# piksi.net
KiCad netlist of a schematic drawn in EAGLE
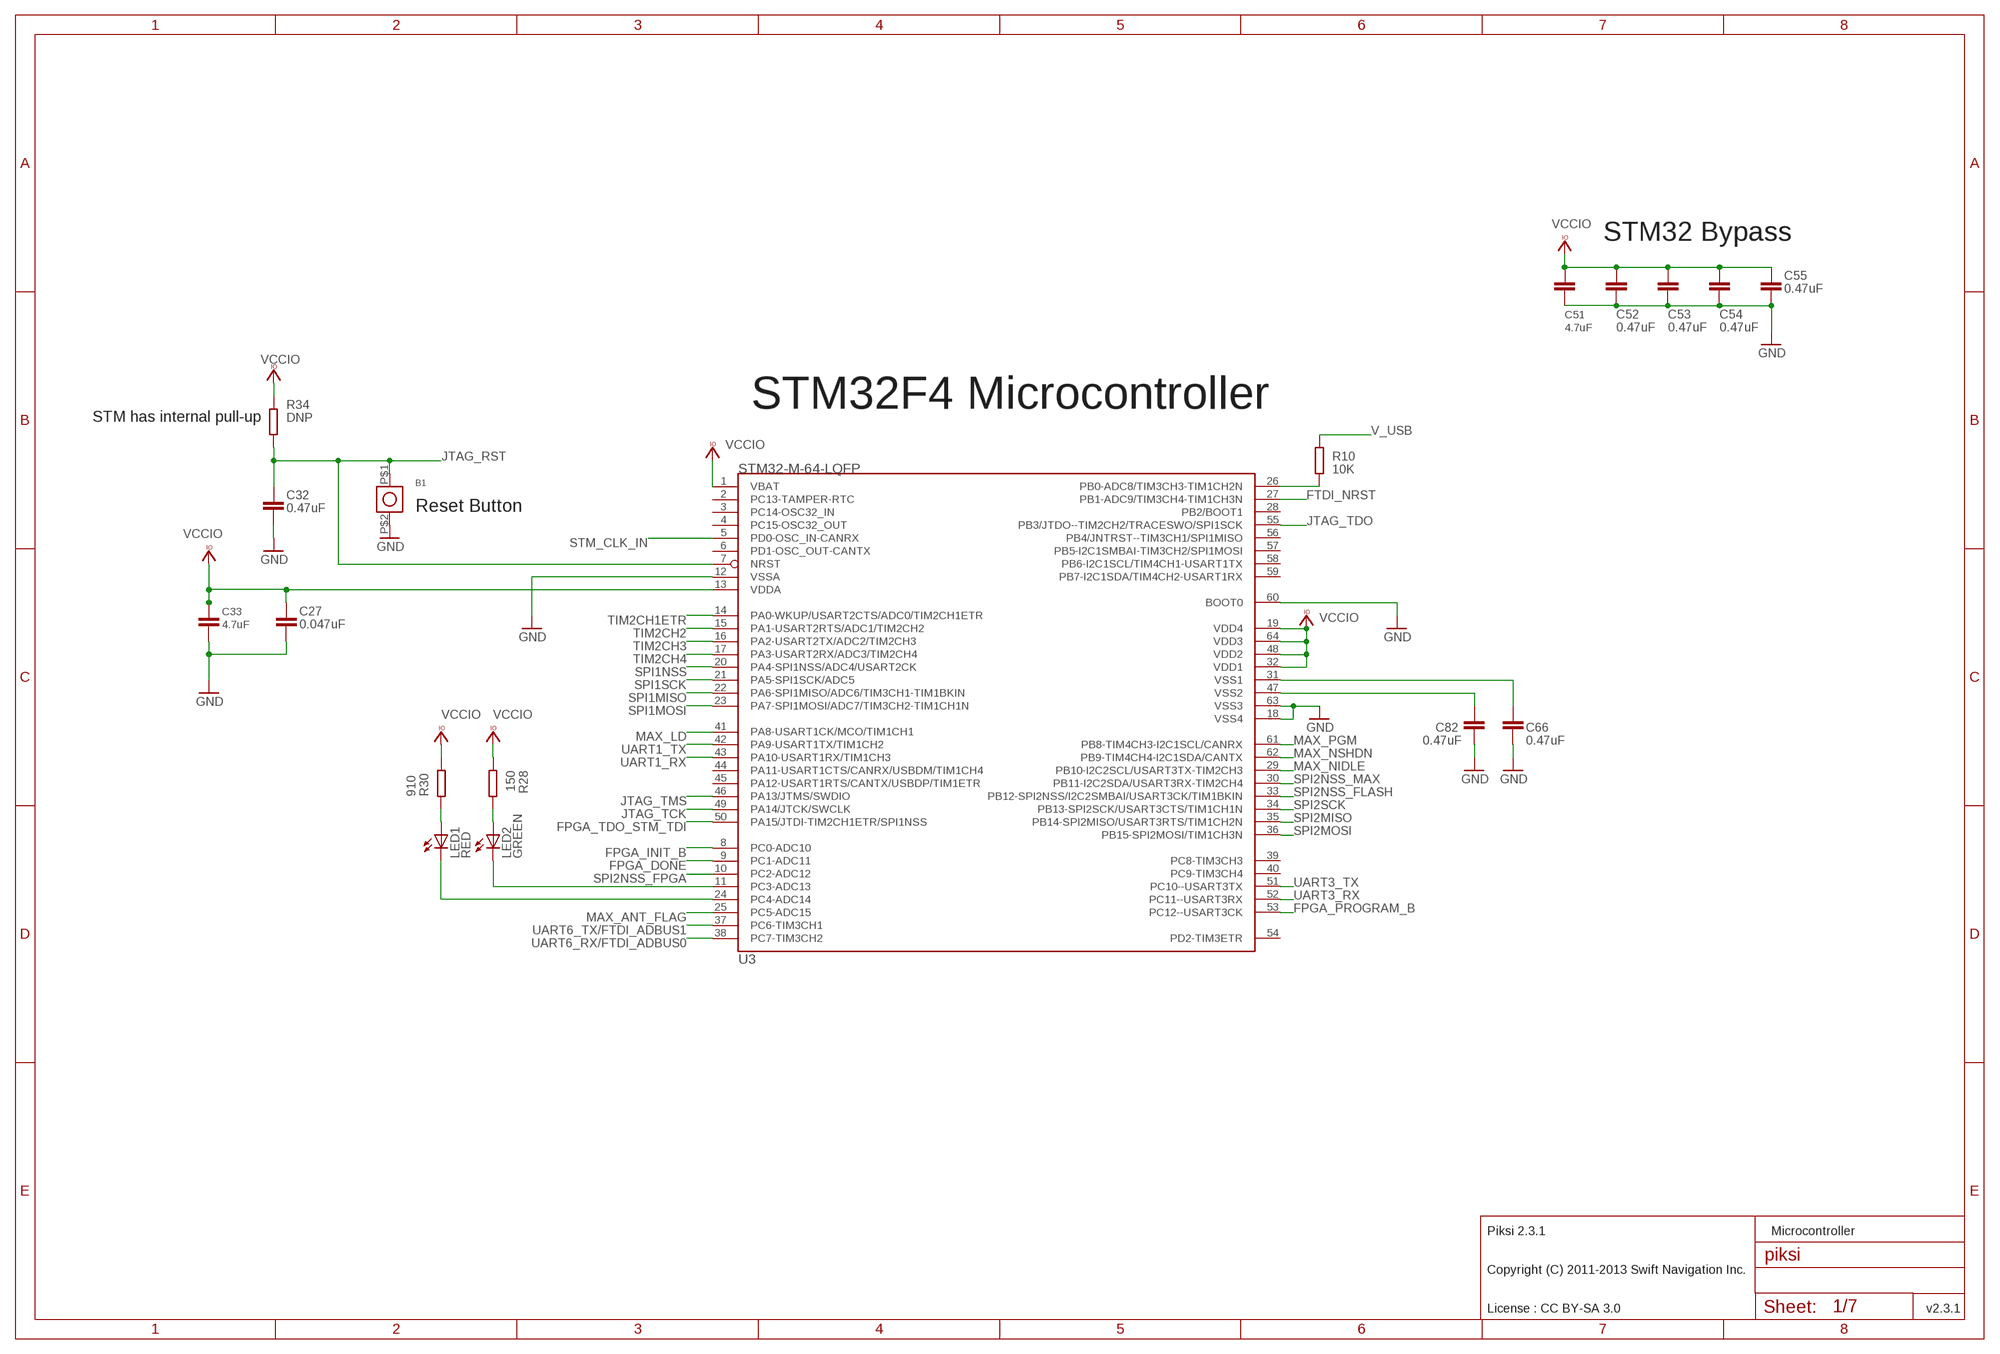
[diagram p0: schematic, sheet 1]
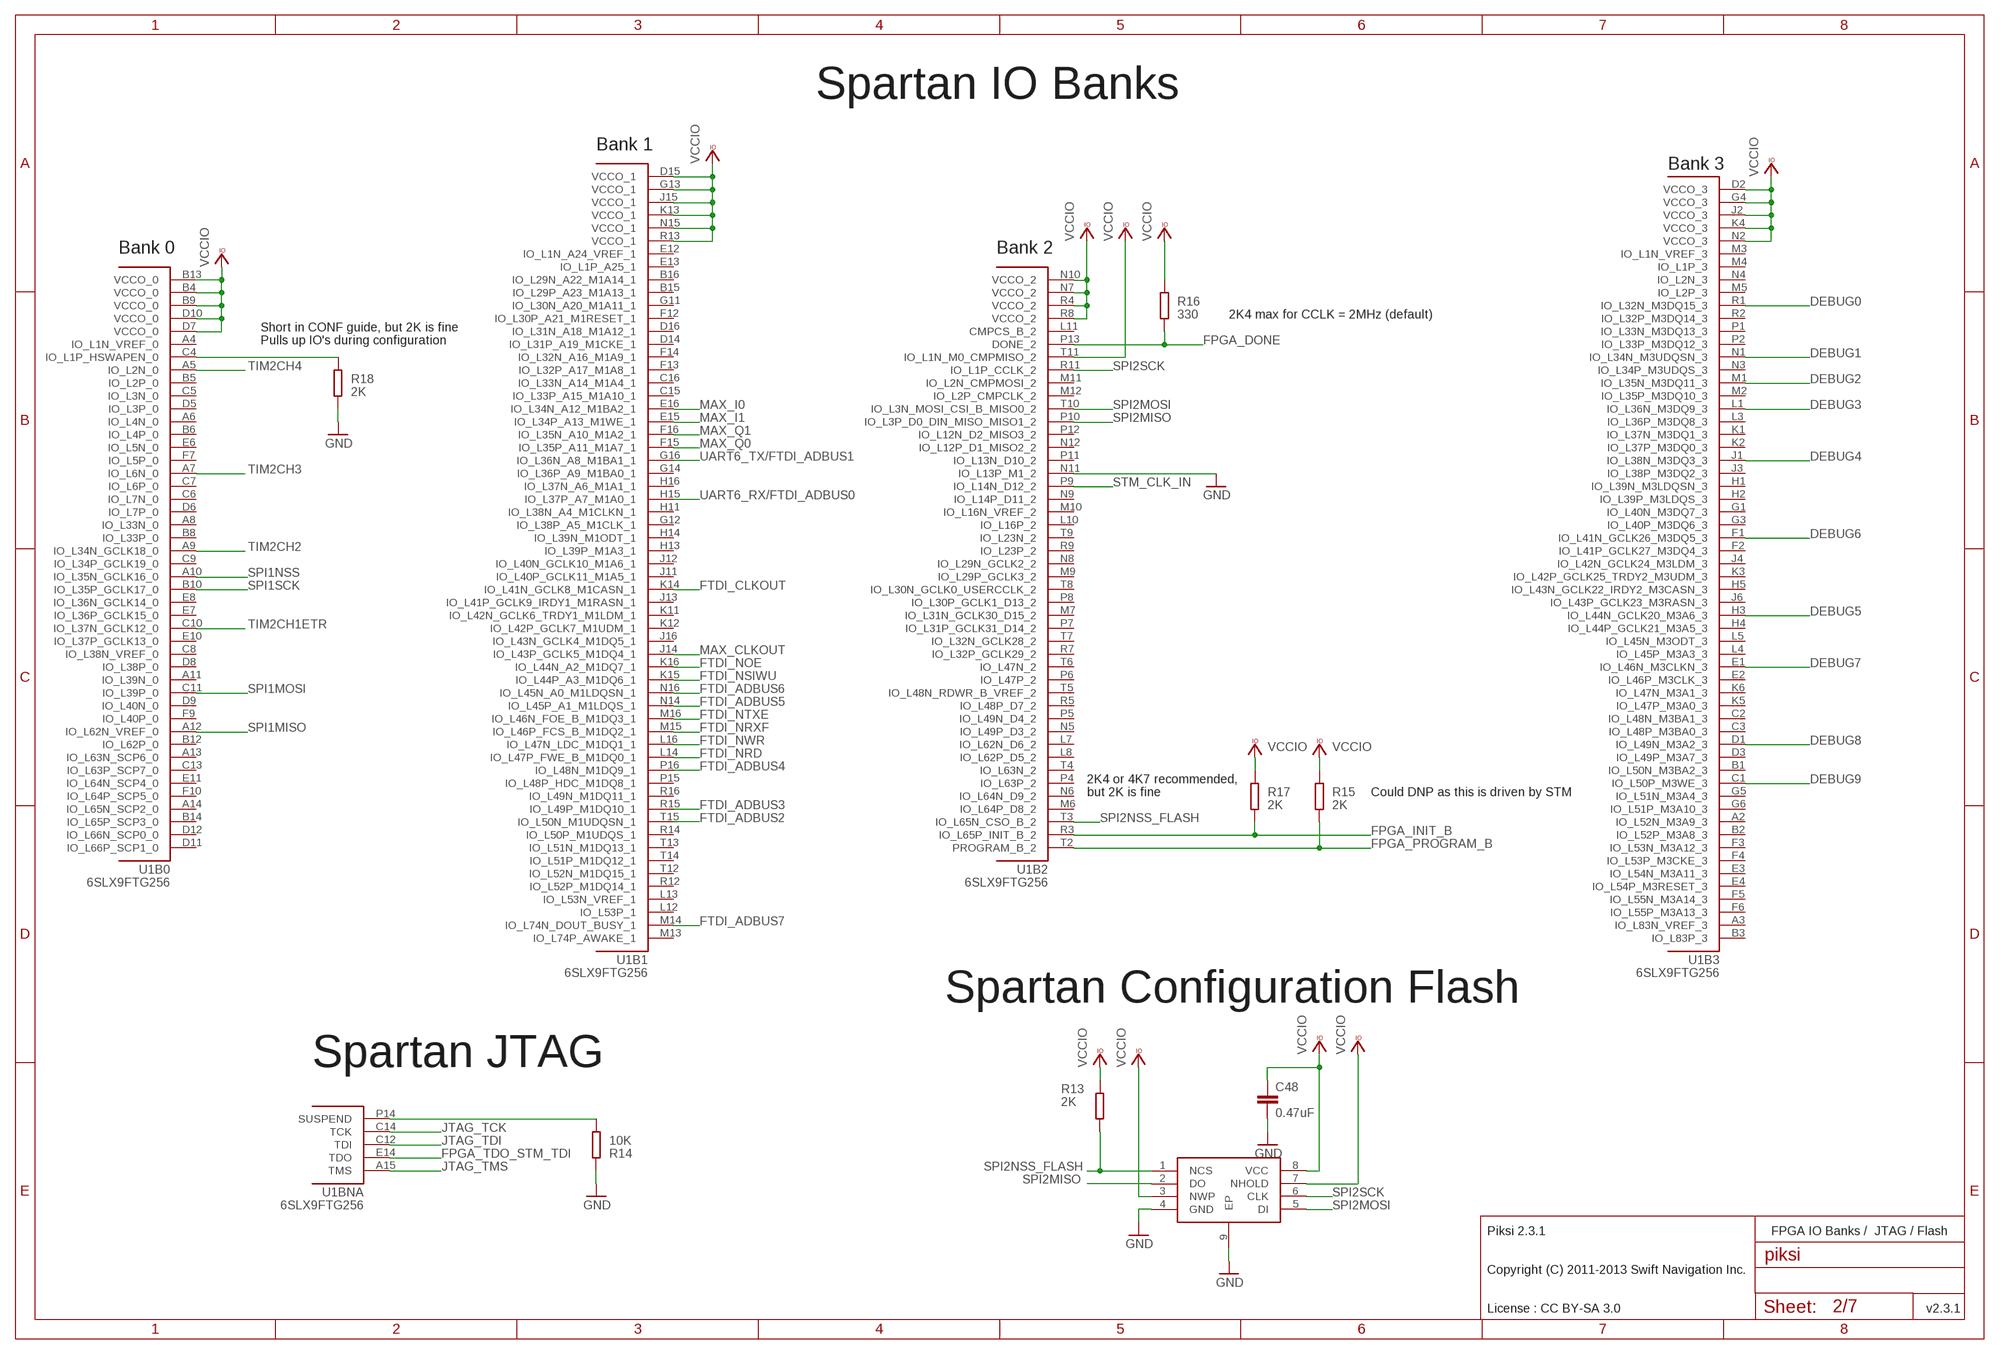
[diagram p1: schematic, sheet 2]
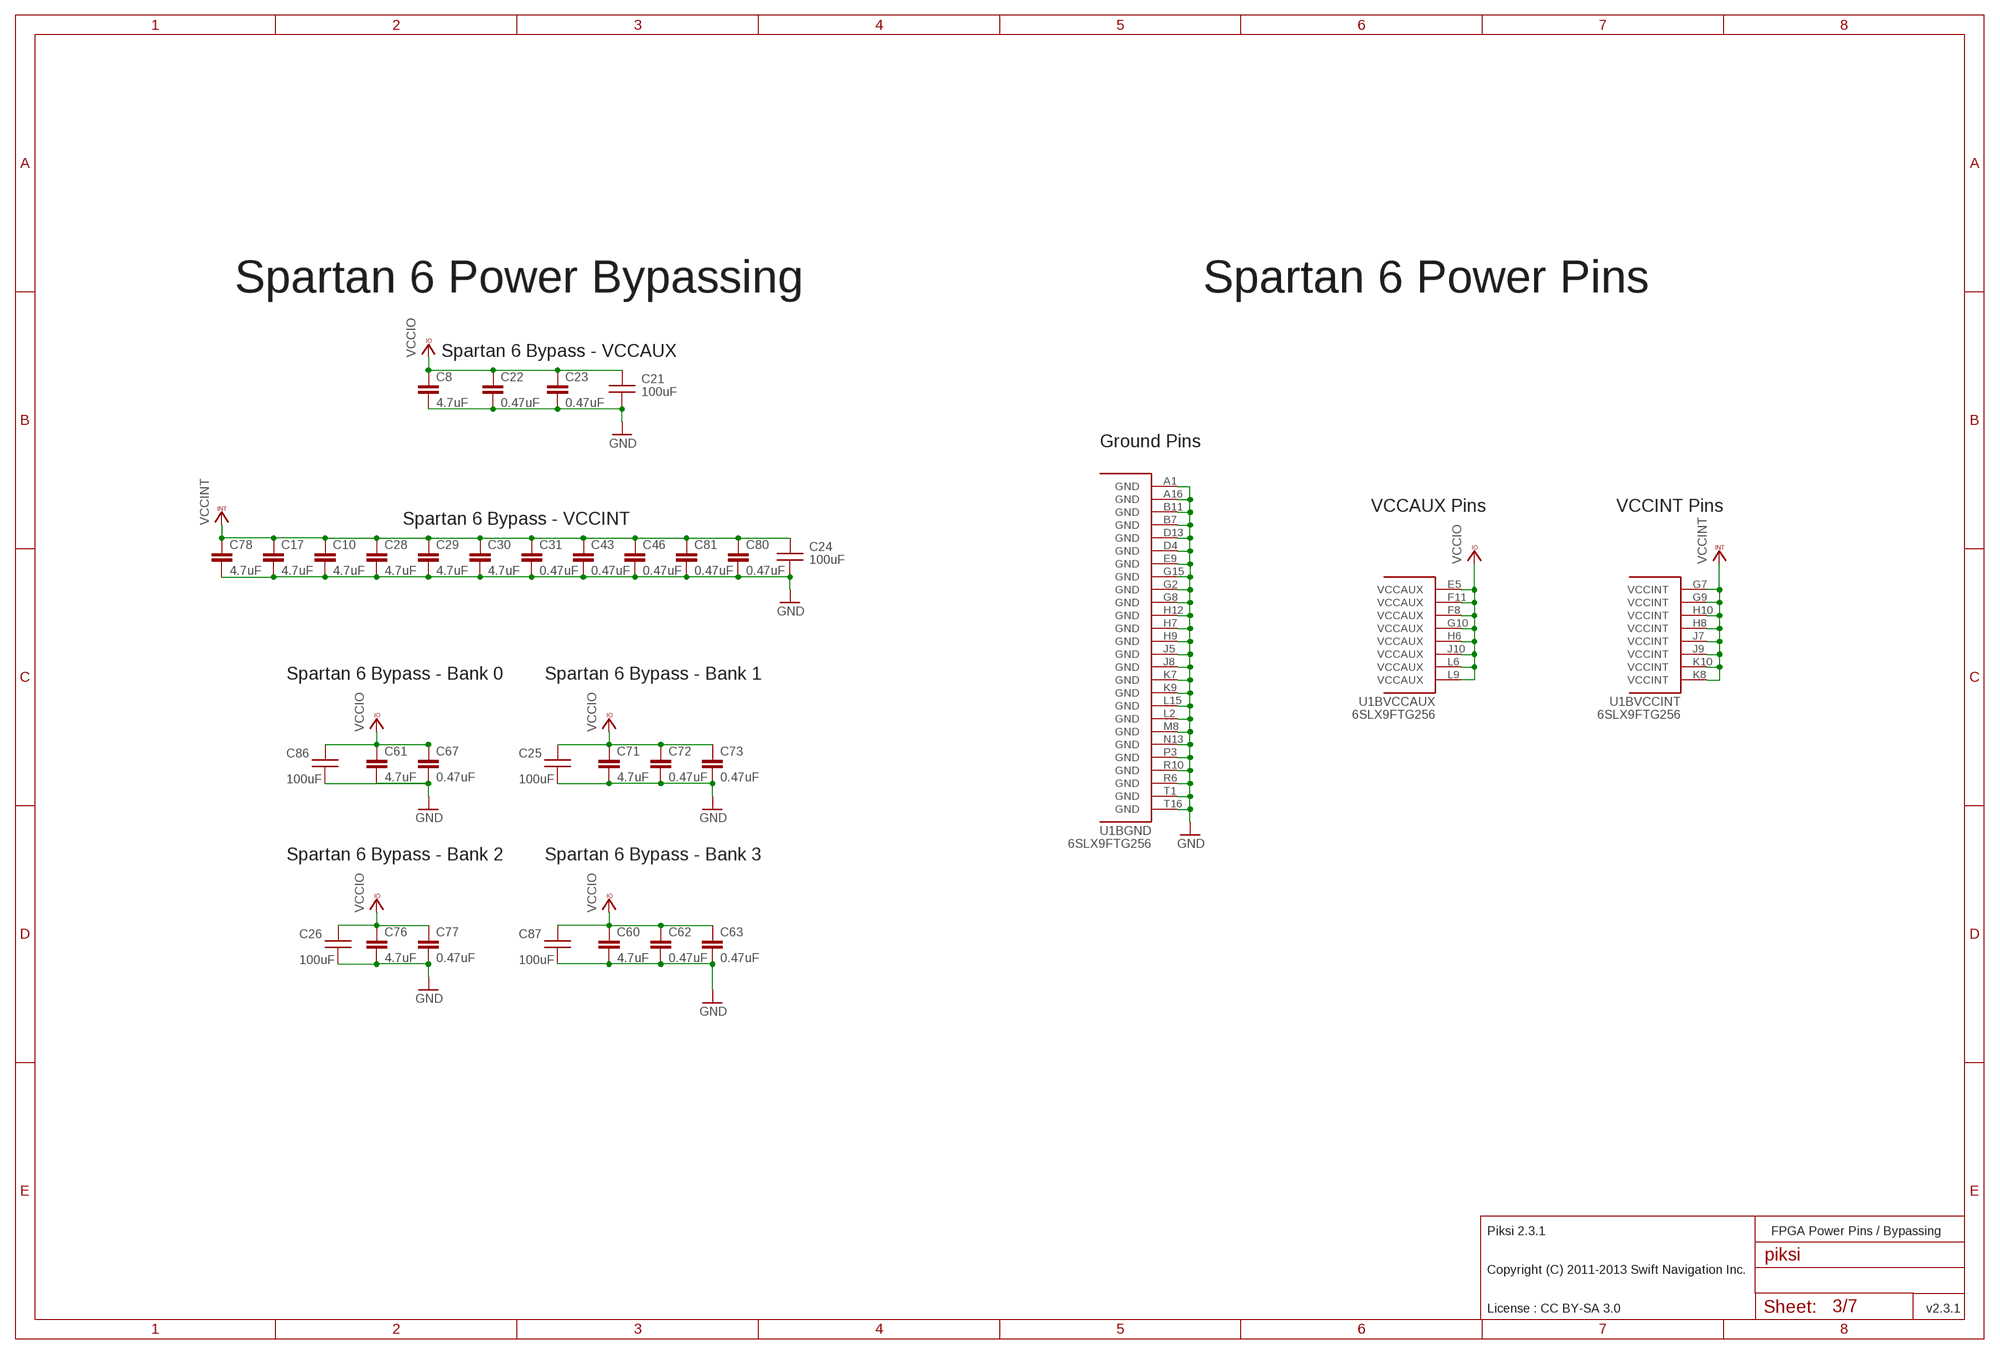
[diagram p2: schematic, sheet 3]
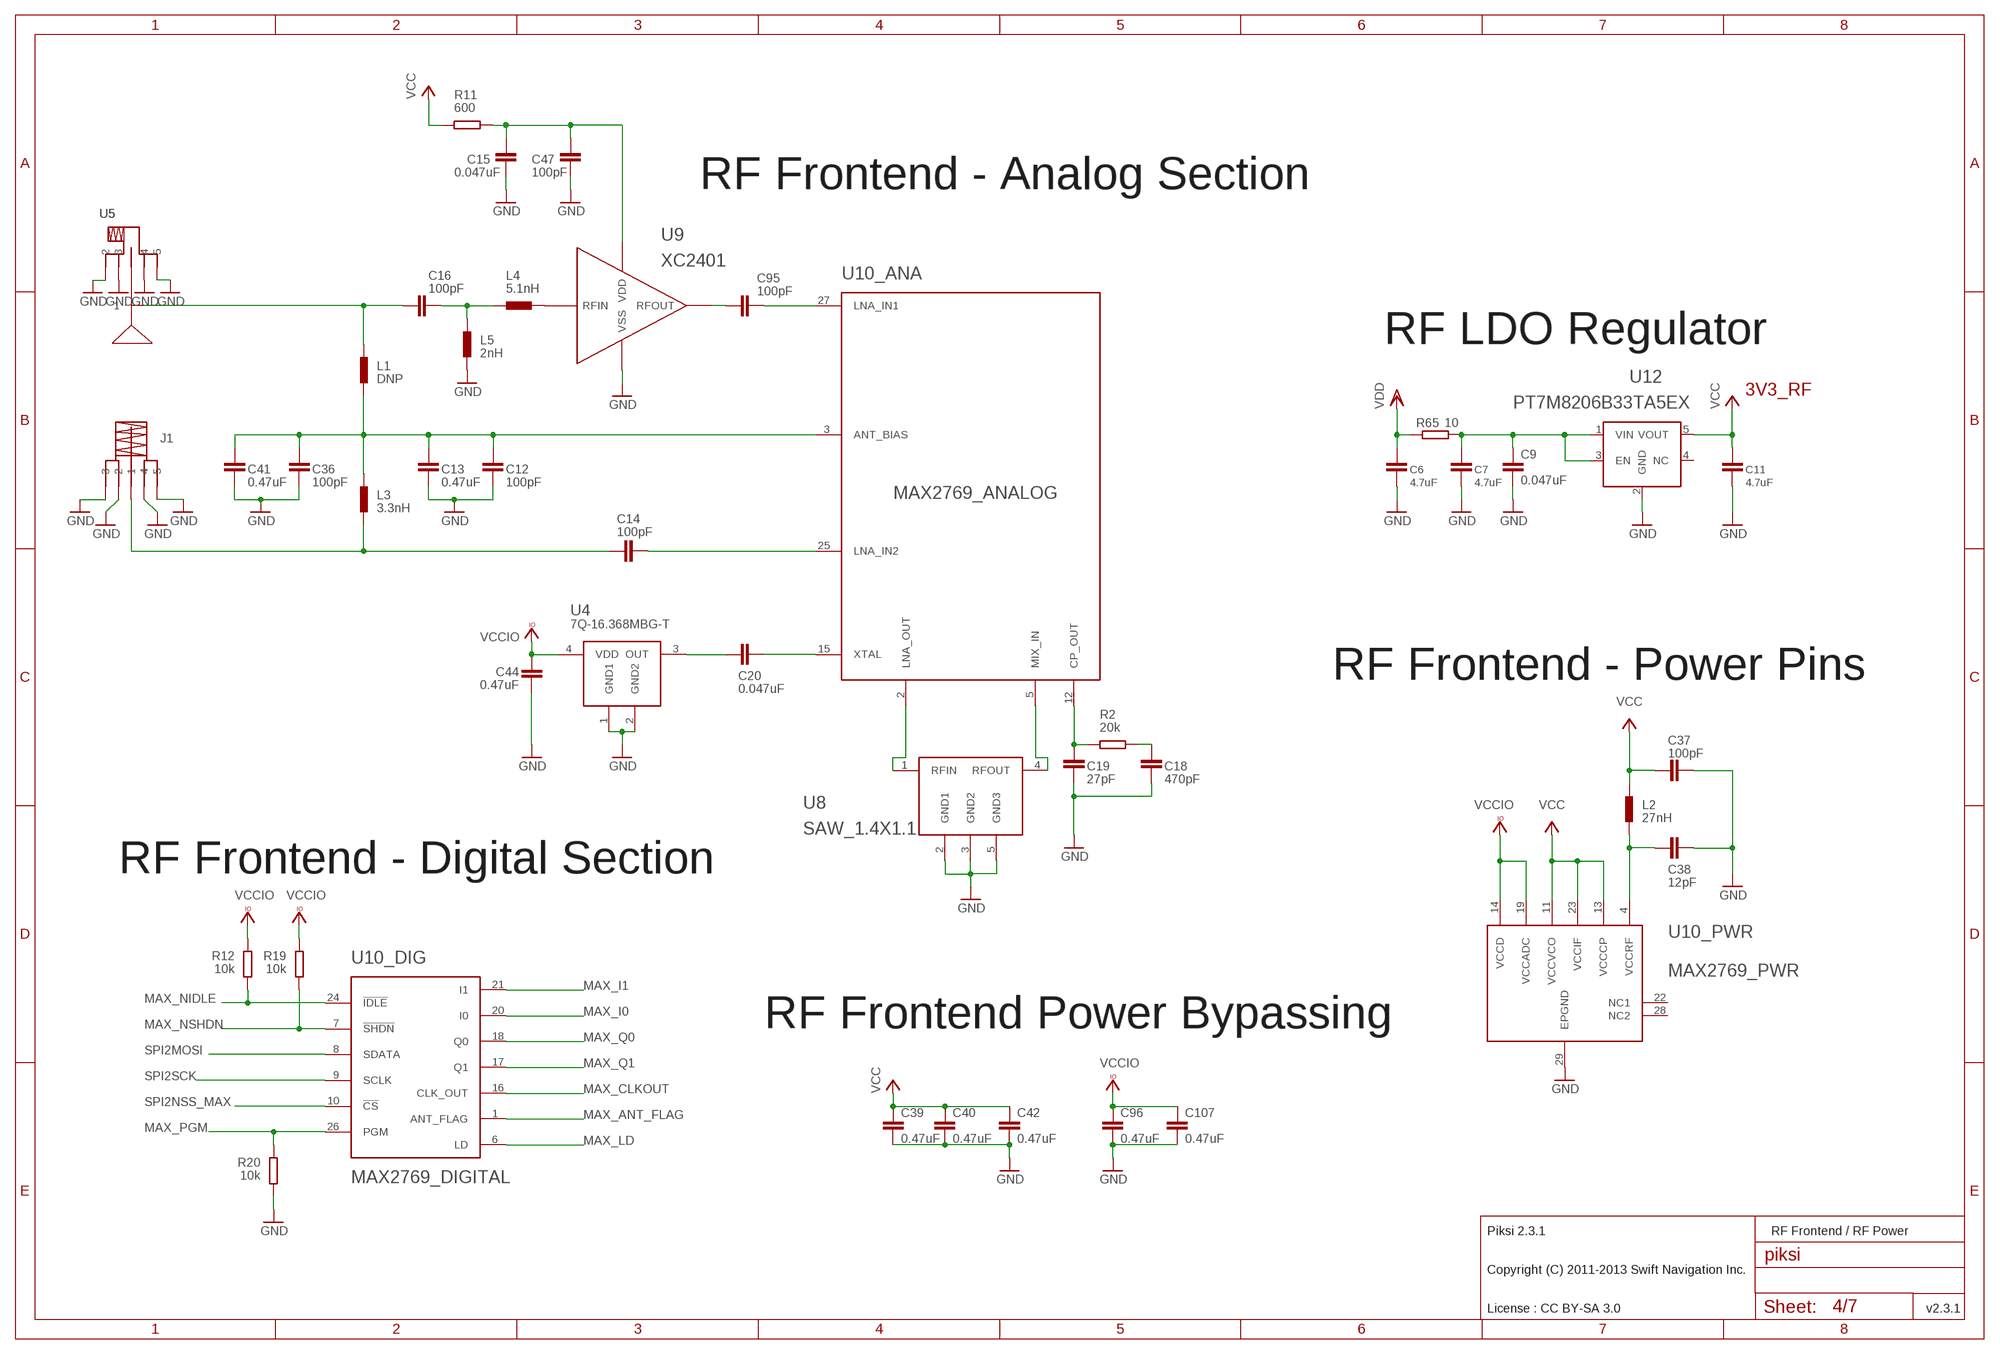
[diagram p3: schematic, sheet 4]
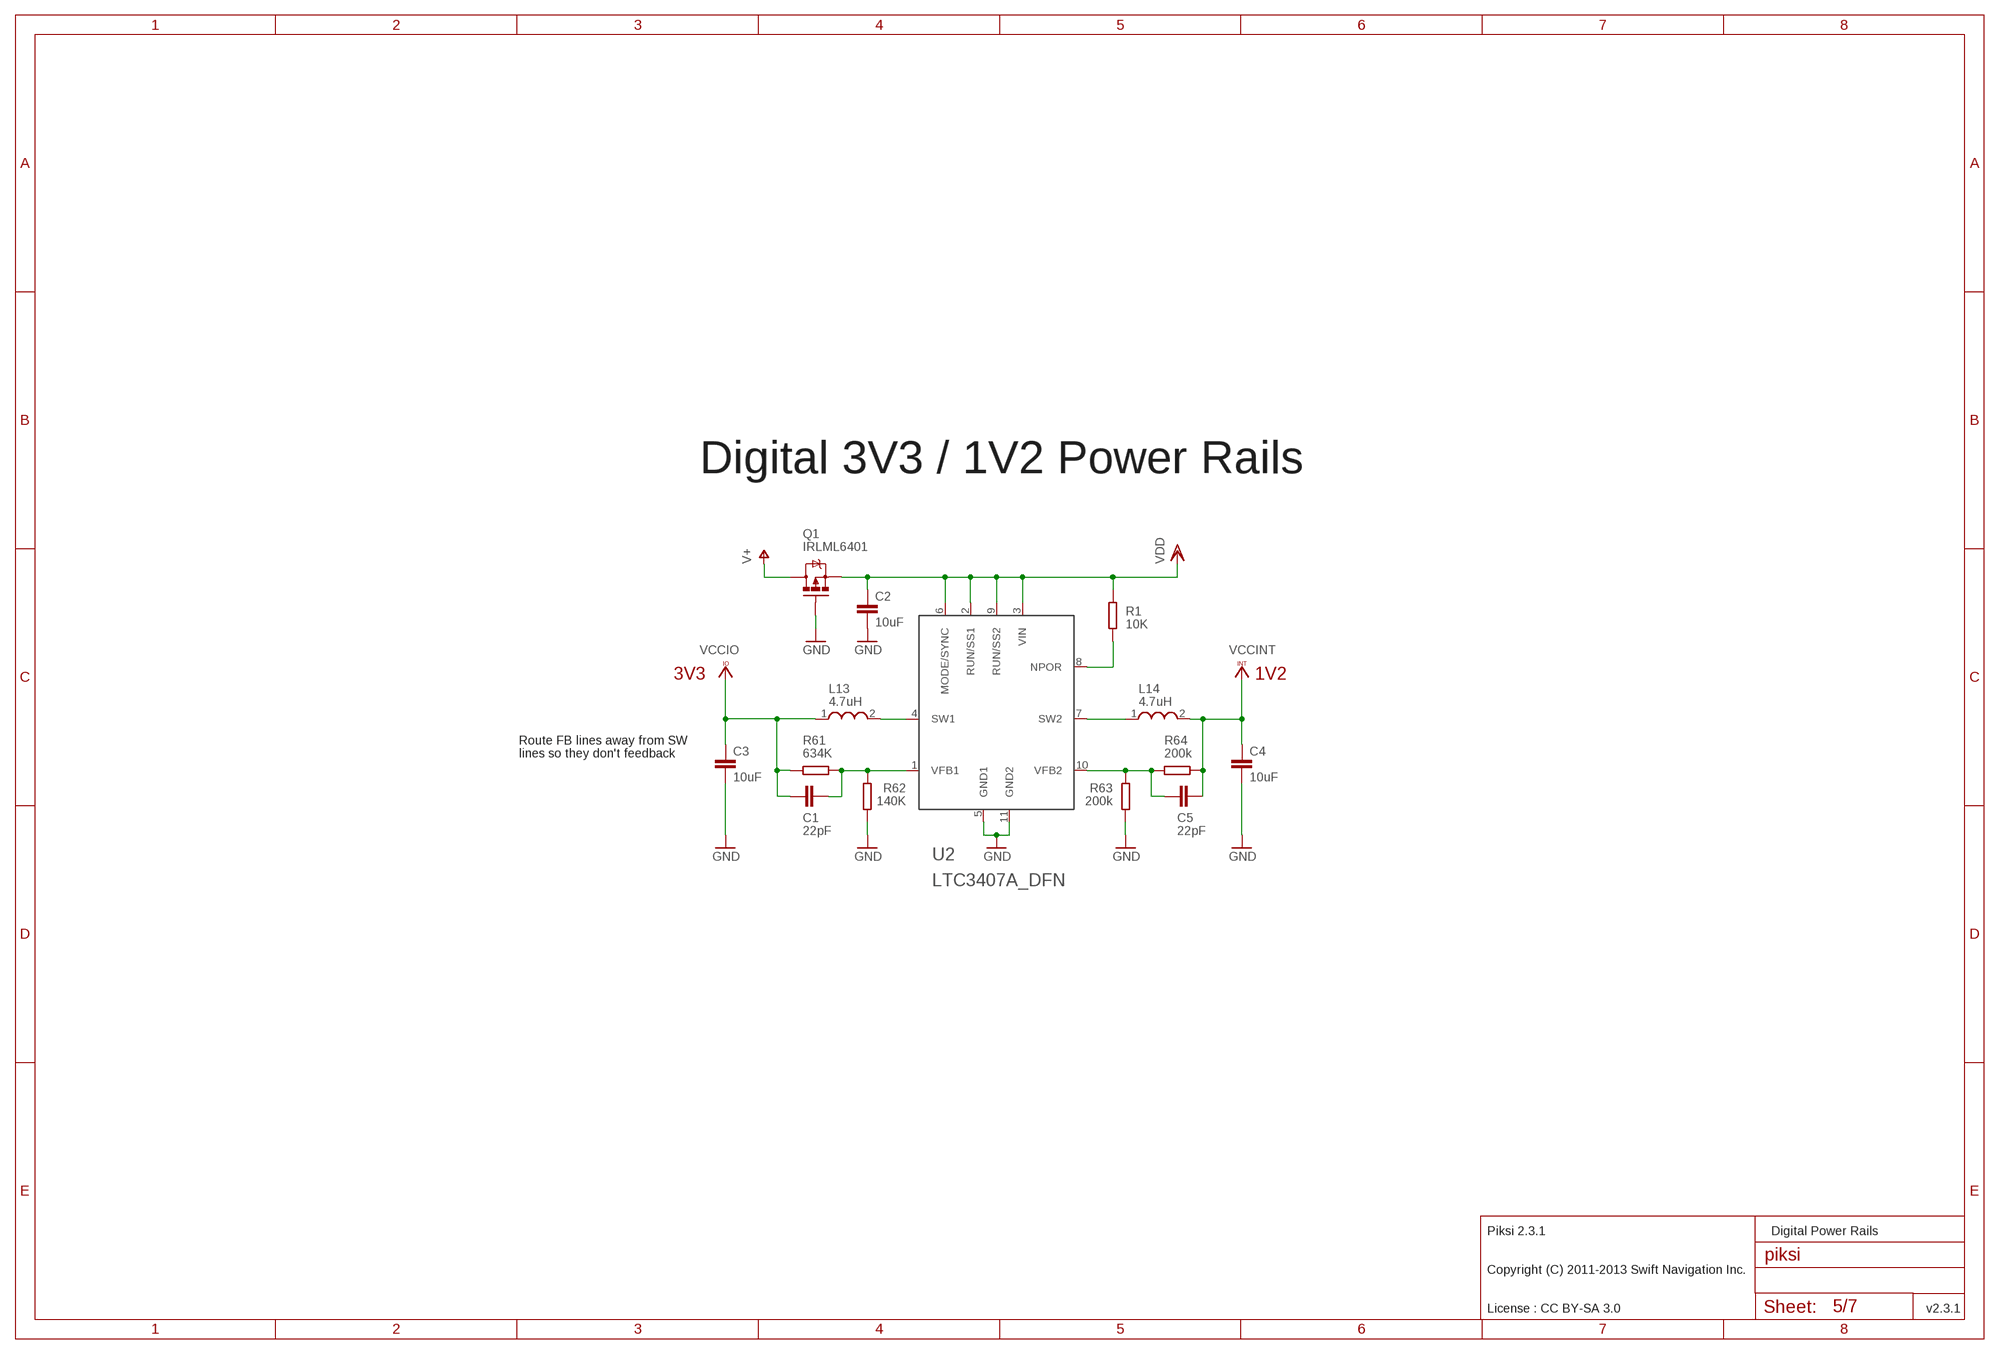
[diagram p4: schematic, sheet 5]
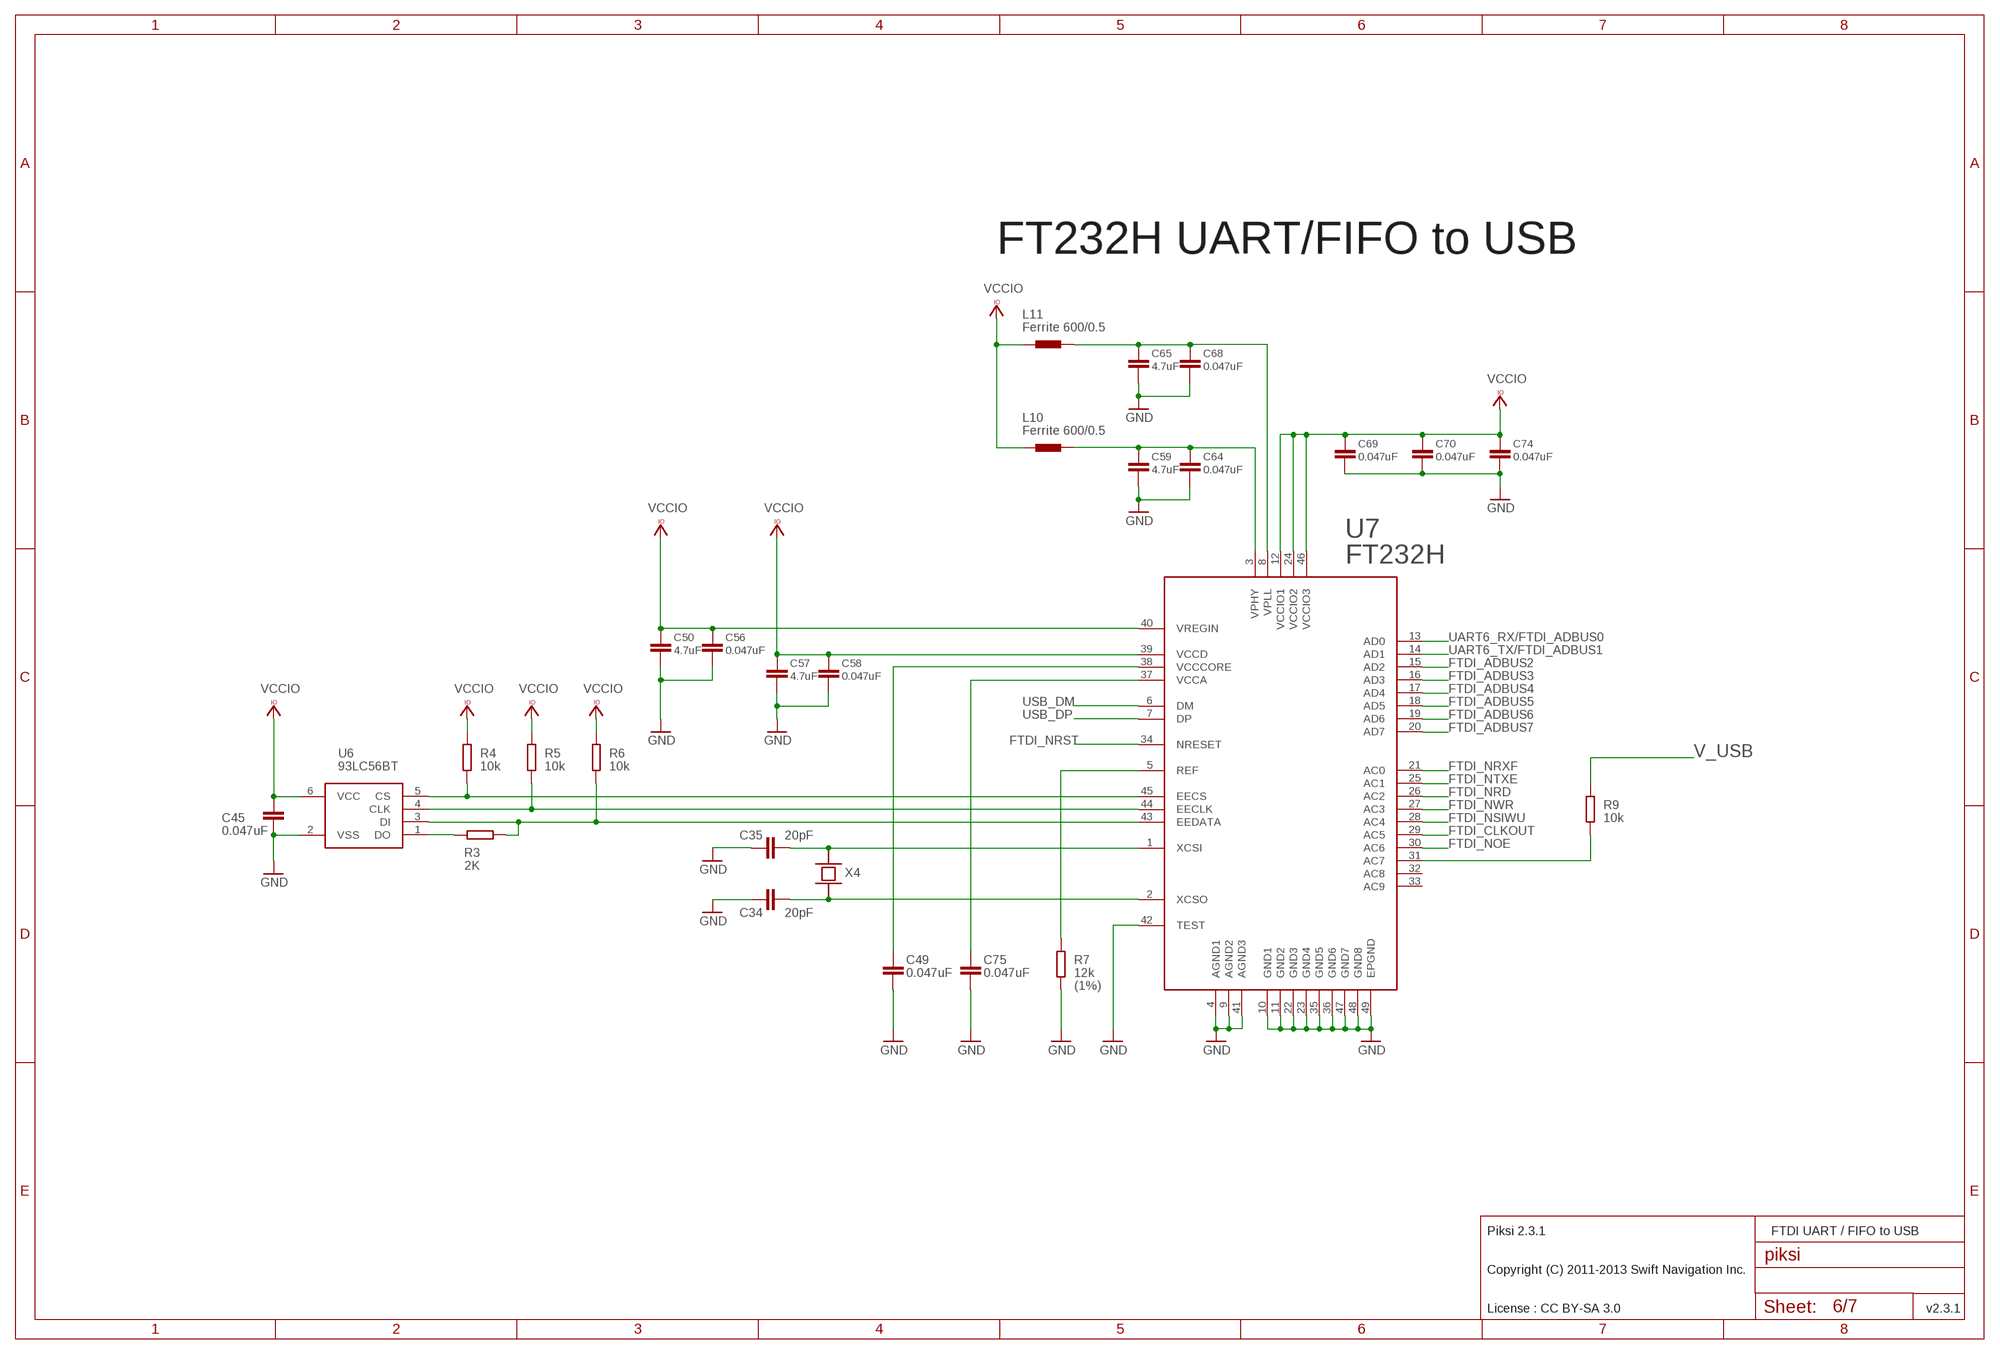
[diagram p5: schematic, sheet 6]
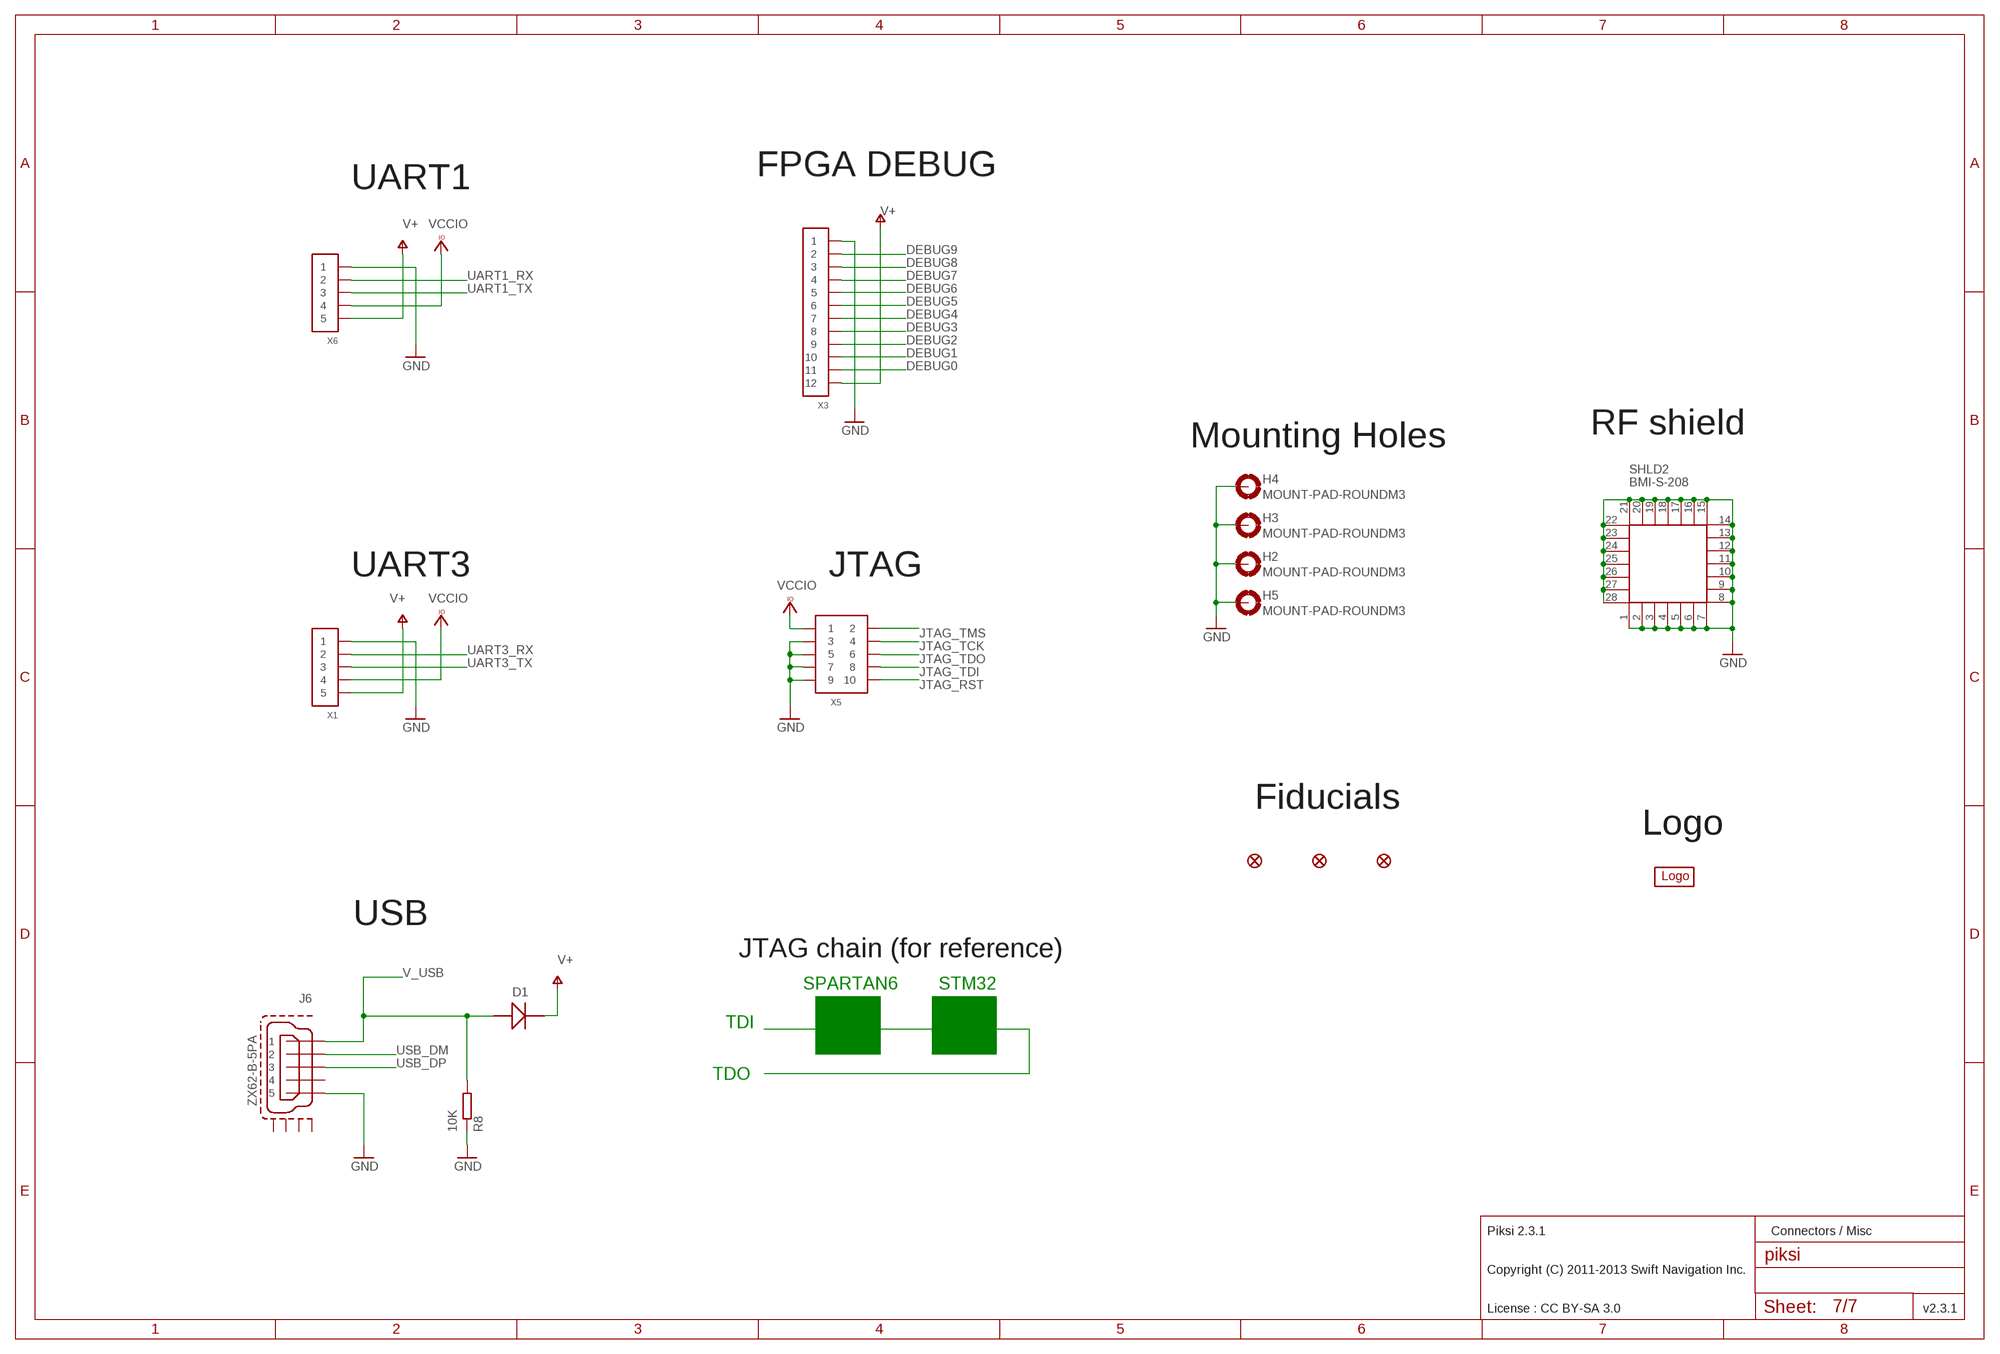
[diagram p6: schematic, sheet 7]

(export (version "E")
  (design (tool "Eeschema 10.0.6"))
  (components
    (comp (ref "D1")
      (value "MBR0520")
      (footprint "eagle-import:SOD-123")
      (libsource (lib "eagle-import") (part "MBR0520"))
    )
    (comp (ref "H2")
      (value "MOUNT-PAD-ROUNDM3")
      (footprint "eagle-import:M3-PAD")
      (libsource (lib "eagle-import") (part "MOUNT-PAD-ROUNDM3"))
    )
    (comp (ref "H3")
      (value "MOUNT-PAD-ROUNDM3")
      (footprint "eagle-import:M3-PAD")
      (libsource (lib "eagle-import") (part "MOUNT-PAD-ROUNDM3"))
    )
    (comp (ref "H4")
      (value "MOUNT-PAD-ROUNDM3")
      (footprint "eagle-import:M3-PAD")
      (libsource (lib "eagle-import") (part "MOUNT-PAD-ROUNDM3"))
    )
    (comp (ref "H5")
      (value "MOUNT-PAD-ROUNDM3")
      (footprint "eagle-import:M3-PAD")
      (libsource (lib "eagle-import") (part "MOUNT-PAD-ROUNDM3"))
    )
    (comp (ref "J6")
      (value "ZX62-B-5PA")
      (footprint "eagle-import:ZX62-B-5PA")
      (libsource (lib "eagle-import") (part "ZX62-B-5PA"))
    )
    (comp (ref "JP8")
      (value "FIDUCIAL1.5X3")
      (footprint "eagle-import:FIDUCIAL-1.5X3")
      (libsource (lib "eagle-import") (part "FIDUCIAL1.5X3"))
    )
    (comp (ref "JP9")
      (value "FIDUCIAL1.5X3")
      (footprint "eagle-import:FIDUCIAL-1.5X3")
      (libsource (lib "eagle-import") (part "FIDUCIAL1.5X3"))
    )
    (comp (ref "JP10")
      (value "FIDUCIAL1.5X3")
      (footprint "eagle-import:FIDUCIAL-1.5X3")
      (libsource (lib "eagle-import") (part "FIDUCIAL1.5X3"))
    )
    (comp (ref "R8")
      (value "10K")
      (footprint "eagle-import:0402-RES")
      (libsource (lib "eagle-import") (part "RESISTOR-0402"))
    )
    (comp (ref "SHLD2")
      (value "BMI-S-208")
      (footprint "eagle-import:BMI-S-208")
      (libsource (lib "eagle-import") (part "BMI-S-208"))
    )
    (comp (ref "U$2")
      (value "LOGOLOGO3_SMALL")
      (footprint "eagle-import:LOGO3_SMALL")
      (libsource (lib "eagle-import") (part "LOGOLOGO3_SMALL"))
    )
    (comp (ref "X1")
      (value "CONN_5-1-53261")
      (footprint "eagle-import:PB-53261-05")
      (libsource (lib "eagle-import") (part "CONN_5-1-53261"))
    )
    (comp (ref "X3")
      (value "FPGA DEBUG")
      (footprint "eagle-import:PB-53261-12")
      (libsource (lib "eagle-import") (part "CONN_12-1-53261"))
    )
    (comp (ref "X5")
      (value "CONN_5-2")
      (footprint "eagle-import:FTSH-105-D")
      (libsource (lib "eagle-import") (part "CONN_5-2"))
    )
    (comp (ref "X6")
      (value "CONN_5-1-53261")
      (footprint "eagle-import:PB-53261-05")
      (libsource (lib "eagle-import") (part "CONN_5-1-53261"))
    )
    (comp (ref "C1")
      (value "22pF")
      (footprint "eagle-import:0402-CAP")
      (libsource (lib "eagle-import") (part "CAPACITOR-0402"))
    )
    (comp (ref "C2")
      (value "10uF")
      (footprint "eagle-import:1206-CAP")
      (libsource (lib "eagle-import") (part "CAPACITOR-1206"))
    )
    (comp (ref "C3")
      (value "10uF")
      (footprint "eagle-import:1206-CAP")
      (libsource (lib "eagle-import") (part "CAPACITOR-1206"))
    )
    (comp (ref "C4")
      (value "10uF")
      (footprint "eagle-import:1206-CAP")
      (libsource (lib "eagle-import") (part "CAPACITOR-1206"))
    )
    (comp (ref "C5")
      (value "22pF")
      (footprint "eagle-import:0402-CAP")
      (libsource (lib "eagle-import") (part "CAPACITOR-0402"))
    )
    (comp (ref "L13")
      (value "4.7uH")
      (footprint "eagle-import:LQM2HPN4R7MG0L")
      (libsource (lib "eagle-import") (part "LQM2HPN4R7MG0L"))
    )
    (comp (ref "L14")
      (value "4.7uH")
      (footprint "eagle-import:LQM2HPN4R7MG0L")
      (libsource (lib "eagle-import") (part "LQM2HPN4R7MG0L"))
    )
    (comp (ref "Q1")
      (value "IRLML6401")
      (footprint "eagle-import:SOT23-3")
      (libsource (lib "eagle-import") (part "MOSFET-PCHANNELSMD"))
    )
    (comp (ref "R1")
      (value "10K")
      (footprint "eagle-import:0402-RES")
      (libsource (lib "eagle-import") (part "RESISTOR-0402"))
    )
    (comp (ref "R61")
      (value "634K")
      (footprint "eagle-import:0402-RES")
      (libsource (lib "eagle-import") (part "RESISTOR-0402"))
    )
    (comp (ref "R62")
      (value "140K")
      (footprint "eagle-import:0402-RES")
      (libsource (lib "eagle-import") (part "RESISTOR-0402"))
    )
    (comp (ref "R63")
      (value "200k")
      (footprint "eagle-import:0402-RES")
      (libsource (lib "eagle-import") (part "RESISTOR-0402"))
    )
    (comp (ref "R64")
      (value "200k")
      (footprint "eagle-import:0402-RES")
      (libsource (lib "eagle-import") (part "RESISTOR-0402"))
    )
    (comp (ref "U2")
      (value "LTC3407A_DFN")
      (footprint "eagle-import:DFN10")
      (libsource (lib "eagle-import") (part "LTC3407A_DFN"))
    )
    (comp (ref "B1")
      (value "B3U-1000P")
      (footprint "eagle-import:B3U-1000P")
      (libsource (lib "eagle-import") (part "B3U-1000P"))
    )
    (comp (ref "C27")
      (value "0.047uF")
      (footprint "eagle-import:0402-CAP")
      (libsource (lib "eagle-import") (part "CAPACITOR-0402"))
    )
    (comp (ref "C32")
      (value "0.47uF")
      (footprint "eagle-import:0402-CAP")
      (libsource (lib "eagle-import") (part "CAPACITOR-0402"))
    )
    (comp (ref "C33")
      (value "4.7uF")
      (footprint "eagle-import:0603-CAP")
      (libsource (lib "eagle-import") (part "CAPACITOR-0603"))
    )
    (comp (ref "C51")
      (value "4.7uF")
      (footprint "eagle-import:0603-CAP")
      (libsource (lib "eagle-import") (part "CAPACITOR-0603"))
    )
    (comp (ref "C52")
      (value "0.47uF")
      (footprint "eagle-import:0402-CAP")
      (libsource (lib "eagle-import") (part "CAPACITOR-0402"))
    )
    (comp (ref "C53")
      (value "0.47uF")
      (footprint "eagle-import:0402-CAP")
      (libsource (lib "eagle-import") (part "CAPACITOR-0402"))
    )
    (comp (ref "C54")
      (value "0.47uF")
      (footprint "eagle-import:0402-CAP")
      (libsource (lib "eagle-import") (part "CAPACITOR-0402"))
    )
    (comp (ref "C55")
      (value "0.47uF")
      (footprint "eagle-import:0402-CAP")
      (libsource (lib "eagle-import") (part "CAPACITOR-0402"))
    )
    (comp (ref "C66")
      (value "0.47uF")
      (footprint "eagle-import:0402-CAP")
      (libsource (lib "eagle-import") (part "CAPACITOR-0402"))
    )
    (comp (ref "C82")
      (value "0.47uF")
      (footprint "eagle-import:0402-CAP")
      (libsource (lib "eagle-import") (part "CAPACITOR-0402"))
    )
    (comp (ref "LED1")
      (value "RED")
      (footprint "eagle-import:0603-LED")
      (libsource (lib "eagle-import") (part "LED-0603"))
    )
    (comp (ref "LED2")
      (value "GREEN")
      (footprint "eagle-import:0603-LED")
      (libsource (lib "eagle-import") (part "LED-0603"))
    )
    (comp (ref "R10")
      (value "10K")
      (footprint "eagle-import:0402-RES")
      (libsource (lib "eagle-import") (part "RESISTOR-0402"))
    )
    (comp (ref "R28")
      (value "150")
      (footprint "eagle-import:0402-RES")
      (libsource (lib "eagle-import") (part "RESISTOR-0402"))
    )
    (comp (ref "R30")
      (value "910")
      (footprint "eagle-import:0402-RES")
      (libsource (lib "eagle-import") (part "RESISTOR-0402"))
    )
    (comp (ref "R34")
      (value "DNP")
      (footprint "eagle-import:0402-RES")
      (libsource (lib "eagle-import") (part "RESISTOR-0402"))
    )
    (comp (ref "U3")
      (value "STM32-M-64-LQFP")
      (footprint "eagle-import:LQFP64")
      (libsource (lib "eagle-import") (part "STM32-M-64-LQFP"))
    )
    (comp (ref "C6")
      (value "4.7uF")
      (footprint "eagle-import:0603-CAP")
      (libsource (lib "eagle-import") (part "CAPACITOR-0603"))
    )
    (comp (ref "C7")
      (value "4.7uF")
      (footprint "eagle-import:0603-CAP")
      (libsource (lib "eagle-import") (part "CAPACITOR-0603"))
    )
    (comp (ref "C9")
      (value "0.047uF")
      (footprint "eagle-import:0402-CAP")
      (libsource (lib "eagle-import") (part "CAPACITOR-0402"))
    )
    (comp (ref "C11")
      (value "4.7uF")
      (footprint "eagle-import:0603-CAP")
      (libsource (lib "eagle-import") (part "CAPACITOR-0603"))
    )
    (comp (ref "C12")
      (value "100pF")
      (footprint "eagle-import:0402-CAP")
      (libsource (lib "eagle-import") (part "CAPACITOR-0402"))
    )
    (comp (ref "C13")
      (value "0.47uF")
      (footprint "eagle-import:0402-CAP")
      (libsource (lib "eagle-import") (part "CAPACITOR-0402"))
    )
    (comp (ref "C14")
      (value "100pF")
      (footprint "eagle-import:0402-CAP")
      (libsource (lib "eagle-import") (part "CAPACITOR-0402"))
    )
    (comp (ref "C15")
      (value "0.047uF")
      (footprint "eagle-import:0402-CAP")
      (libsource (lib "eagle-import") (part "CAPACITOR-0402"))
    )
    (comp (ref "C16")
      (value "100pF")
      (footprint "eagle-import:0402-CAP")
      (libsource (lib "eagle-import") (part "CAPACITOR-0402"))
    )
    (comp (ref "C18")
      (value "470pF")
      (footprint "eagle-import:0402-CAP")
      (libsource (lib "eagle-import") (part "CAPACITOR-0402"))
    )
    (comp (ref "C19")
      (value "27pF")
      (footprint "eagle-import:0402-CAP")
      (libsource (lib "eagle-import") (part "CAPACITOR-0402"))
    )
    (comp (ref "C20")
      (value "0.047uF")
      (footprint "eagle-import:0402-CAP")
      (libsource (lib "eagle-import") (part "CAPACITOR-0402"))
    )
    (comp (ref "C36")
      (value "100pF")
      (footprint "eagle-import:0402-CAP")
      (libsource (lib "eagle-import") (part "CAPACITOR-0402"))
    )
    (comp (ref "C37")
      (value "100pF")
      (footprint "eagle-import:0402-CAP")
      (libsource (lib "eagle-import") (part "CAPACITOR-0402"))
    )
    (comp (ref "C38")
      (value "12pF")
      (footprint "eagle-import:0402-CAP")
      (libsource (lib "eagle-import") (part "CAPACITOR-0402"))
    )
    (comp (ref "C39")
      (value "0.47uF")
      (footprint "eagle-import:0402-CAP")
      (libsource (lib "eagle-import") (part "CAPACITOR-0402"))
    )
    (comp (ref "C40")
      (value "0.47uF")
      (footprint "eagle-import:0402-CAP")
      (libsource (lib "eagle-import") (part "CAPACITOR-0402"))
    )
    (comp (ref "C41")
      (value "0.47uF")
      (footprint "eagle-import:0402-CAP")
      (libsource (lib "eagle-import") (part "CAPACITOR-0402"))
    )
    (comp (ref "C42")
      (value "0.47uF")
      (footprint "eagle-import:0402-CAP")
      (libsource (lib "eagle-import") (part "CAPACITOR-0402"))
    )
    (comp (ref "C44")
      (value "0.47uF")
      (footprint "eagle-import:0402-CAP")
      (libsource (lib "eagle-import") (part "CAPACITOR-0402"))
    )
    (comp (ref "C47")
      (value "100pF")
      (footprint "eagle-import:0402-CAP")
      (libsource (lib "eagle-import") (part "CAPACITOR-0402"))
    )
    (comp (ref "C95")
      (value "100pF")
      (footprint "eagle-import:0402-CAP")
      (libsource (lib "eagle-import") (part "CAPACITOR-0402"))
    )
    (comp (ref "C96")
      (value "0.47uF")
      (footprint "eagle-import:0402-CAP")
      (libsource (lib "eagle-import") (part "CAPACITOR-0402"))
    )
    (comp (ref "C107")
      (value "0.47uF")
      (footprint "eagle-import:0402-CAP")
      (libsource (lib "eagle-import") (part "CAPACITOR-0402"))
    )
    (comp (ref "J1")
      (value "SMA_EDGE")
      (footprint "eagle-import:SMA_EDGE")
      (libsource (lib "eagle-import") (part "SMA_EDGE"))
    )
    (comp (ref "L1")
      (value "DNP")
      (footprint "eagle-import:0402-IND")
      (libsource (lib "eagle-import") (part "INDUCTOR-0402"))
    )
    (comp (ref "L2")
      (value "27nH")
      (footprint "eagle-import:0402-IND")
      (libsource (lib "eagle-import") (part "INDUCTOR-0402"))
    )
    (comp (ref "L3")
      (value "3.3nH")
      (footprint "eagle-import:0402-IND")
      (libsource (lib "eagle-import") (part "INDUCTOR-0402"))
    )
    (comp (ref "L4")
      (value "5.1nH")
      (footprint "eagle-import:0402-IND")
      (libsource (lib "eagle-import") (part "INDUCTOR-0402"))
    )
    (comp (ref "L5")
      (value "2nH")
      (footprint "eagle-import:0402-IND")
      (libsource (lib "eagle-import") (part "INDUCTOR-0402"))
    )
    (comp (ref "R2")
      (value "20k")
      (footprint "eagle-import:0402-RES")
      (libsource (lib "eagle-import") (part "RESISTOR-0402"))
    )
    (comp (ref "R11")
      (value "600")
      (footprint "eagle-import:0402-RES")
      (libsource (lib "eagle-import") (part "RESISTOR-0402"))
    )
    (comp (ref "R12")
      (value "10k")
      (footprint "eagle-import:0402-RES")
      (libsource (lib "eagle-import") (part "RESISTOR-0402"))
    )
    (comp (ref "R19")
      (value "10k")
      (footprint "eagle-import:0402-RES")
      (libsource (lib "eagle-import") (part "RESISTOR-0402"))
    )
    (comp (ref "R20")
      (value "10k")
      (footprint "eagle-import:0402-RES")
      (libsource (lib "eagle-import") (part "RESISTOR-0402"))
    )
    (comp (ref "R65")
      (value "10")
      (footprint "eagle-import:0402-RES")
      (libsource (lib "eagle-import") (part "RESISTOR-0402"))
    )
    (comp (ref "U4")
      (value "7Q-16.368MBG-T")
      (footprint "eagle-import:TCX_7Q")
      (libsource (lib "eagle-import") (part "7Q-16.368MBG-T"))
    )
    (comp (ref "U5")
      (value "SMA_PATCH_SMDGND")
      (footprint "eagle-import:SMA_PATCH_SMDGND")
      (libsource (lib "eagle-import") (part "SMA_PATCH_SMDGND"))
    )
    (comp (ref "U8")
      (value "SAW_1.4X1.1")
      (footprint "eagle-import:SAW_1.4X1.1")
      (libsource (lib "eagle-import") (part "SAW_1.4X1.1"))
    )
    (comp (ref "U9")
      (value "XC2401")
      (footprint "eagle-import:XC2401")
      (libsource (lib "eagle-import") (part "XC2401"))
    )
    (comp (ref "U10")
      (value "MAX2769")
      (footprint "eagle-import:MAX2769")
      (libsource (lib "eagle-import") (part "MAX2769"))
    )
    (comp (ref "U12")
      (value "PT7M8206B33TA5EX")
      (footprint "eagle-import:PT7M8206B33TA5EX")
      (libsource (lib "eagle-import") (part "PT7M8206B33TA5EX"))
    )
    (comp (ref "C48")
      (value "0.47uF")
      (footprint "eagle-import:0402-CAP")
      (libsource (lib "eagle-import") (part "CAPACITOR-0402"))
    )
    (comp (ref "R13")
      (value "2K")
      (footprint "eagle-import:0402-RES")
      (libsource (lib "eagle-import") (part "RESISTOR-0402"))
    )
    (comp (ref "R14")
      (value "10K")
      (footprint "eagle-import:0402-RES")
      (libsource (lib "eagle-import") (part "RESISTOR-0402"))
    )
    (comp (ref "R15")
      (value "2K")
      (footprint "eagle-import:0402-RES")
      (libsource (lib "eagle-import") (part "RESISTOR-0402"))
    )
    (comp (ref "R16")
      (value "330")
      (footprint "eagle-import:0402-RES")
      (libsource (lib "eagle-import") (part "RESISTOR-0402"))
    )
    (comp (ref "R17")
      (value "2K")
      (footprint "eagle-import:0402-RES")
      (libsource (lib "eagle-import") (part "RESISTOR-0402"))
    )
    (comp (ref "R18")
      (value "2K")
      (footprint "eagle-import:0402-RES")
      (libsource (lib "eagle-import") (part "RESISTOR-0402"))
    )
    (comp (ref "U1")
      (value "6SLX9FTG256")
      (footprint "eagle-import:FT256")
      (libsource (lib "eagle-import") (part "6SLX9FTG256"))
    )
    (comp (ref "U13")
      (value "M25PX80")
      (footprint "eagle-import:M25P80_MLP8")
      (libsource (lib "eagle-import") (part "M25P80_MLP8"))
    )
    (comp (ref "C34")
      (value "20pF")
      (footprint "eagle-import:0402-CAP")
      (libsource (lib "eagle-import") (part "CAPACITOR-0402"))
    )
    (comp (ref "C35")
      (value "20pF")
      (footprint "eagle-import:0402-CAP")
      (libsource (lib "eagle-import") (part "CAPACITOR-0402"))
    )
    (comp (ref "C45")
      (value "0.047uF")
      (footprint "eagle-import:C0402")
      (libsource (lib "eagle-import") (part "C-EUC0402"))
    )
    (comp (ref "C49")
      (value "0.047uF")
      (footprint "eagle-import:0402-CAP")
      (libsource (lib "eagle-import") (part "CAPACITOR-0402"))
    )
    (comp (ref "C50")
      (value "4.7uF")
      (footprint "eagle-import:0603-CAP")
      (libsource (lib "eagle-import") (part "CAPACITOR-0603"))
    )
    (comp (ref "C56")
      (value "0.047uF")
      (footprint "eagle-import:0402-CAP")
      (libsource (lib "eagle-import") (part "CAPACITOR-0402"))
    )
    (comp (ref "C57")
      (value "4.7uF")
      (footprint "eagle-import:0603-CAP")
      (libsource (lib "eagle-import") (part "CAPACITOR-0603"))
    )
    (comp (ref "C58")
      (value "0.047uF")
      (footprint "eagle-import:0402-CAP")
      (libsource (lib "eagle-import") (part "CAPACITOR-0402"))
    )
    (comp (ref "C59")
      (value "4.7uF")
      (footprint "eagle-import:0603-CAP")
      (libsource (lib "eagle-import") (part "CAPACITOR-0603"))
    )
    (comp (ref "C64")
      (value "0.047uF")
      (footprint "eagle-import:0402-CAP")
      (libsource (lib "eagle-import") (part "CAPACITOR-0402"))
    )
    (comp (ref "C65")
      (value "4.7uF")
      (footprint "eagle-import:0603-CAP")
      (libsource (lib "eagle-import") (part "CAPACITOR-0603"))
    )
    (comp (ref "C68")
      (value "0.047uF")
      (footprint "eagle-import:0402-CAP")
      (libsource (lib "eagle-import") (part "CAPACITOR-0402"))
    )
    (comp (ref "C69")
      (value "0.047uF")
      (footprint "eagle-import:C0603K")
      (libsource (lib "eagle-import") (part "C-EUC0603K"))
    )
    (comp (ref "C70")
      (value "0.047uF")
      (footprint "eagle-import:0402-CAP")
      (libsource (lib "eagle-import") (part "CAPACITOR-0402"))
    )
    (comp (ref "C74")
      (value "0.047uF")
      (footprint "eagle-import:0402-CAP")
      (libsource (lib "eagle-import") (part "CAPACITOR-0402"))
    )
    (comp (ref "C75")
      (value "0.047uF")
      (footprint "eagle-import:0402-CAP")
      (libsource (lib "eagle-import") (part "CAPACITOR-0402"))
    )
    (comp (ref "L10")
      (value "Ferrite 600/0.5")
      (footprint "eagle-import:0805-IND")
      (libsource (lib "eagle-import") (part "INDUCTOR-0805"))
    )
    (comp (ref "L11")
      (value "Ferrite 600/0.5")
      (footprint "eagle-import:0805-IND")
      (libsource (lib "eagle-import") (part "INDUCTOR-0805"))
    )
    (comp (ref "R3")
      (value "2K")
      (footprint "eagle-import:0402-RES")
      (libsource (lib "eagle-import") (part "RESISTOR-0402"))
    )
    (comp (ref "R4")
      (value "10k")
      (footprint "eagle-import:0402-RES")
      (libsource (lib "eagle-import") (part "RESISTOR-0402"))
    )
    (comp (ref "R5")
      (value "10k")
      (footprint "eagle-import:0402-RES")
      (libsource (lib "eagle-import") (part "RESISTOR-0402"))
    )
    (comp (ref "R6")
      (value "10k")
      (footprint "eagle-import:0402-RES")
      (libsource (lib "eagle-import") (part "RESISTOR-0402"))
    )
    (comp (ref "R7")
      (value "12k")
      (footprint "eagle-import:0402-RES")
      (libsource (lib "eagle-import") (part "RESISTOR-0402"))
    )
    (comp (ref "R9")
      (value "10k")
      (footprint "eagle-import:0402-RES")
      (libsource (lib "eagle-import") (part "RESISTOR-0402"))
    )
    (comp (ref "U6")
      (value "93LC56BT-I/OT")
      (footprint "eagle-import:93AA56BT-I_OT")
      (libsource (lib "eagle-import") (part "93LC56BT-I/OT"))
    )
    (comp (ref "U7")
      (value "FT232HQ")
      (footprint "eagle-import:FT232HQ")
      (libsource (lib "eagle-import") (part "FT232HQ"))
    )
    (comp (ref "X4")
      (value "NX5032GA-12M")
      (footprint "eagle-import:NX5032GA")
      (libsource (lib "eagle-import") (part "NX5032GA-12M"))
    )
    (comp (ref "C8")
      (value "4.7uF")
      (footprint "eagle-import:0603-CAP")
      (libsource (lib "eagle-import") (part "CAPACITOR-0603"))
    )
    (comp (ref "C10")
      (value "4.7uF")
      (footprint "eagle-import:0603-CAP")
      (libsource (lib "eagle-import") (part "CAPACITOR-0603"))
    )
    (comp (ref "C17")
      (value "4.7uF")
      (footprint "eagle-import:0603-CAP")
      (libsource (lib "eagle-import") (part "CAPACITOR-0603"))
    )
    (comp (ref "C21")
      (value "100uF")
      (footprint "eagle-import:C1210")
      (libsource (lib "eagle-import") (part "C1210"))
    )
    (comp (ref "C22")
      (value "0.47uF")
      (footprint "eagle-import:0402-CAP")
      (libsource (lib "eagle-import") (part "CAPACITOR-0402"))
    )
    (comp (ref "C23")
      (value "0.47uF")
      (footprint "eagle-import:0402-CAP")
      (libsource (lib "eagle-import") (part "CAPACITOR-0402"))
    )
    (comp (ref "C24")
      (value "100uF")
      (footprint "eagle-import:C1210")
      (libsource (lib "eagle-import") (part "C1210"))
    )
    (comp (ref "C25")
      (value "100uF")
      (footprint "eagle-import:C1210")
      (libsource (lib "eagle-import") (part "C1210"))
    )
    (comp (ref "C26")
      (value "100uF")
      (footprint "eagle-import:C1210")
      (libsource (lib "eagle-import") (part "C1210"))
    )
    (comp (ref "C28")
      (value "4.7uF")
      (footprint "eagle-import:0603-CAP")
      (libsource (lib "eagle-import") (part "CAPACITOR-0603"))
    )
    (comp (ref "C29")
      (value "4.7uF")
      (footprint "eagle-import:0603-CAP")
      (libsource (lib "eagle-import") (part "CAPACITOR-0603"))
    )
    (comp (ref "C30")
      (value "4.7uF")
      (footprint "eagle-import:0603-CAP")
      (libsource (lib "eagle-import") (part "CAPACITOR-0603"))
    )
    (comp (ref "C31")
      (value "0.47uF")
      (footprint "eagle-import:0402-CAP")
      (libsource (lib "eagle-import") (part "CAPACITOR-0402"))
    )
    (comp (ref "C43")
      (value "0.47uF")
      (footprint "eagle-import:0402-CAP")
      (libsource (lib "eagle-import") (part "CAPACITOR-0402"))
    )
    (comp (ref "C46")
      (value "0.47uF")
      (footprint "eagle-import:0402-CAP")
      (libsource (lib "eagle-import") (part "CAPACITOR-0402"))
    )
    (comp (ref "C60")
      (value "4.7uF")
      (footprint "eagle-import:0603-CAP")
      (libsource (lib "eagle-import") (part "CAPACITOR-0603"))
    )
    (comp (ref "C61")
      (value "4.7uF")
      (footprint "eagle-import:0603-CAP")
      (libsource (lib "eagle-import") (part "CAPACITOR-0603"))
    )
    (comp (ref "C62")
      (value "0.47uF")
      (footprint "eagle-import:0402-CAP")
      (libsource (lib "eagle-import") (part "CAPACITOR-0402"))
    )
    (comp (ref "C63")
      (value "0.47uF")
      (footprint "eagle-import:0402-CAP")
      (libsource (lib "eagle-import") (part "CAPACITOR-0402"))
    )
    (comp (ref "C67")
      (value "0.47uF")
      (footprint "eagle-import:0402-CAP")
      (libsource (lib "eagle-import") (part "CAPACITOR-0402"))
    )
    (comp (ref "C71")
      (value "4.7uF")
      (footprint "eagle-import:0603-CAP")
      (libsource (lib "eagle-import") (part "CAPACITOR-0603"))
    )
    (comp (ref "C72")
      (value "0.47uF")
      (footprint "eagle-import:0402-CAP")
      (libsource (lib "eagle-import") (part "CAPACITOR-0402"))
    )
    (comp (ref "C73")
      (value "0.47uF")
      (footprint "eagle-import:0402-CAP")
      (libsource (lib "eagle-import") (part "CAPACITOR-0402"))
    )
    (comp (ref "C76")
      (value "4.7uF")
      (footprint "eagle-import:0603-CAP")
      (libsource (lib "eagle-import") (part "CAPACITOR-0603"))
    )
    (comp (ref "C77")
      (value "0.47uF")
      (footprint "eagle-import:0402-CAP")
      (libsource (lib "eagle-import") (part "CAPACITOR-0402"))
    )
    (comp (ref "C78")
      (value "4.7uF")
      (footprint "eagle-import:0603-CAP")
      (libsource (lib "eagle-import") (part "CAPACITOR-0603"))
    )
    (comp (ref "C80")
      (value "0.47uF")
      (footprint "eagle-import:0402-CAP")
      (libsource (lib "eagle-import") (part "CAPACITOR-0402"))
    )
    (comp (ref "C81")
      (value "0.47uF")
      (footprint "eagle-import:0402-CAP")
      (libsource (lib "eagle-import") (part "CAPACITOR-0402"))
    )
    (comp (ref "C86")
      (value "100uF")
      (footprint "eagle-import:C1210")
      (libsource (lib "eagle-import") (part "C1210"))
    )
    (comp (ref "C87")
      (value "100uF")
      (footprint "eagle-import:C1210")
      (libsource (lib "eagle-import") (part "C1210"))
    )
  )
  (nets
    (net (code "1") (name "DEBUG0") (class "Default")
      (node (ref "U1") (pin "R1") (pinfunction "IO_L32N_M3DQ15_3_R1") (pintype "bidirectional"))
      (node (ref "X3") (pin "11") (pinfunction "11_11") (pintype "bidirectional"))
    )
    (net (code "2") (name "DEBUG1") (class "Default")
      (node (ref "U1") (pin "N1") (pinfunction "IO_L34N_M3UDQSN_3_N1") (pintype "bidirectional"))
      (node (ref "X3") (pin "10") (pinfunction "10_10") (pintype "bidirectional"))
    )
    (net (code "3") (name "DEBUG2") (class "Default")
      (node (ref "U1") (pin "M1") (pinfunction "IO_L35N_M3DQ11_3_M1") (pintype "bidirectional"))
      (node (ref "X3") (pin "9") (pinfunction "9_9") (pintype "bidirectional"))
    )
    (net (code "4") (name "DEBUG3") (class "Default")
      (node (ref "U1") (pin "L1") (pinfunction "IO_L36N_M3DQ9_3_L1") (pintype "bidirectional"))
      (node (ref "X3") (pin "8") (pinfunction "8_8") (pintype "bidirectional"))
    )
    (net (code "5") (name "DEBUG4") (class "Default")
      (node (ref "U1") (pin "J1") (pinfunction "IO_L38N_M3DQ3_3_J1") (pintype "bidirectional"))
      (node (ref "X3") (pin "7") (pinfunction "7_7") (pintype "bidirectional"))
    )
    (net (code "6") (name "DEBUG5") (class "Default")
      (node (ref "U1") (pin "H3") (pinfunction "IO_L44N_GCLK20_M3A6_3_H3") (pintype "bidirectional"))
      (node (ref "X3") (pin "6") (pinfunction "6_6") (pintype "bidirectional"))
    )
    (net (code "7") (name "DEBUG6") (class "Default")
      (node (ref "U1") (pin "F1") (pinfunction "IO_L41N_GCLK26_M3DQ5_3_F1") (pintype "bidirectional"))
      (node (ref "X3") (pin "5") (pinfunction "5_5") (pintype "bidirectional"))
    )
    (net (code "8") (name "DEBUG7") (class "Default")
      (node (ref "U1") (pin "E1") (pinfunction "IO_L46N_M3CLKN_3_E1") (pintype "bidirectional"))
      (node (ref "X3") (pin "4") (pinfunction "4_4") (pintype "bidirectional"))
    )
    (net (code "9") (name "DEBUG8") (class "Default")
      (node (ref "U1") (pin "D1") (pinfunction "IO_L49N_M3A2_3_D1") (pintype "bidirectional"))
      (node (ref "X3") (pin "3") (pinfunction "3_3") (pintype "bidirectional"))
    )
    (net (code "10") (name "DEBUG9") (class "Default")
      (node (ref "U1") (pin "C1") (pinfunction "IO_L50P_M3WE_3_C1") (pintype "bidirectional"))
      (node (ref "X3") (pin "2") (pinfunction "2_2") (pintype "bidirectional"))
    )
    (net (code "11") (name "FPGA_DONE") (class "Default")
      (node (ref "R16") (pin "P$1") (pinfunction "1_P$1") (pintype "passive"))
      (node (ref "U1") (pin "P13") (pinfunction "DONE_2_P13") (pintype "bidirectional"))
      (node (ref "U3") (pin "9") (pinfunction "PC1-ADC11_9") (pintype "bidirectional"))
    )
    (net (code "12") (name "FPGA_INIT_B") (class "Default")
      (node (ref "R17") (pin "P$2") (pinfunction "2_P$2") (pintype "passive"))
      (node (ref "U1") (pin "R3") (pinfunction "IO_L65P_INIT_B_2_R3") (pintype "bidirectional"))
      (node (ref "U3") (pin "8") (pinfunction "PC0-ADC10_8") (pintype "bidirectional"))
    )
    (net (code "13") (name "FPGA_PROGRAM_B") (class "Default")
      (node (ref "R15") (pin "P$2") (pinfunction "2_P$2") (pintype "passive"))
      (node (ref "U1") (pin "T2") (pinfunction "PROGRAM_B_2_T2") (pintype "input"))
      (node (ref "U3") (pin "53") (pinfunction "PC12--USART3CK_53") (pintype "bidirectional"))
    )
    (net (code "14") (name "FPGA_TDO_STM_TDI") (class "Default")
      (node (ref "U1") (pin "E14") (pinfunction "TDO_E14") (pintype "output"))
      (node (ref "U3") (pin "50") (pinfunction "PA15/JTDI-TIM2CH1ETR/SPI1NSS_50") (pintype "bidirectional"))
    )
    (net (code "15") (name "FTDI_ADBUS2") (class "Default")
      (node (ref "U1") (pin "T15") (pinfunction "IO_L50N_M1UDQSN_1_T15") (pintype "bidirectional"))
      (node (ref "U7") (pin "15") (pinfunction "AD2_15") (pintype "bidirectional"))
    )
    (net (code "16") (name "FTDI_ADBUS3") (class "Default")
      (node (ref "U1") (pin "R15") (pinfunction "IO_L49P_M1DQ10_1_R15") (pintype "bidirectional"))
      (node (ref "U7") (pin "16") (pinfunction "AD3_16") (pintype "bidirectional"))
    )
    (net (code "17") (name "FTDI_ADBUS4") (class "Default")
      (node (ref "U1") (pin "P16") (pinfunction "IO_L48N_M1DQ9_1_P16") (pintype "bidirectional"))
      (node (ref "U7") (pin "17") (pinfunction "AD4_17") (pintype "bidirectional"))
    )
    (net (code "18") (name "FTDI_ADBUS5") (class "Default")
      (node (ref "U1") (pin "N14") (pinfunction "IO_L45P_A1_M1LDQS_1_N14") (pintype "bidirectional"))
      (node (ref "U7") (pin "18") (pinfunction "AD5_18") (pintype "bidirectional"))
    )
    (net (code "19") (name "FTDI_ADBUS6") (class "Default")
      (node (ref "U1") (pin "N16") (pinfunction "IO_L45N_A0_M1LDQSN_1_N16") (pintype "bidirectional"))
      (node (ref "U7") (pin "19") (pinfunction "AD6_19") (pintype "bidirectional"))
    )
    (net (code "20") (name "FTDI_ADBUS7") (class "Default")
      (node (ref "U1") (pin "M14") (pinfunction "IO_L74N_DOUT_BUSY_1_M14") (pintype "bidirectional"))
      (node (ref "U7") (pin "20") (pinfunction "AD7_20") (pintype "bidirectional"))
    )
    (net (code "21") (name "FTDI_CLKOUT") (class "Default")
      (node (ref "U1") (pin "K14") (pinfunction "IO_L41N_GCLK8_M1CASN_1_K14") (pintype "bidirectional"))
      (node (ref "U7") (pin "29") (pinfunction "AC5_29") (pintype "bidirectional"))
    )
    (net (code "22") (name "FTDI_NOE") (class "Default")
      (node (ref "U1") (pin "K16") (pinfunction "IO_L44N_A2_M1DQ7_1_K16") (pintype "bidirectional"))
      (node (ref "U7") (pin "30") (pinfunction "AC6_30") (pintype "bidirectional"))
    )
    (net (code "23") (name "FTDI_NRD") (class "Default")
      (node (ref "U1") (pin "L14") (pinfunction "IO_L47P_FWE_B_M1DQ0_1_L14") (pintype "bidirectional"))
      (node (ref "U7") (pin "26") (pinfunction "AC2_26") (pintype "bidirectional"))
    )
    (net (code "24") (name "FTDI_NRST") (class "Default")
      (node (ref "U3") (pin "27") (pinfunction "PB1-ADC9/TIM3CH4-TIM1CH3N_27") (pintype "bidirectional"))
      (node (ref "U7") (pin "34") (pinfunction "NRESET_34") (pintype "input"))
    )
    (net (code "25") (name "FTDI_NRXF") (class "Default")
      (node (ref "U1") (pin "M15") (pinfunction "IO_L46P_FCS_B_M1DQ2_1_M15") (pintype "bidirectional"))
      (node (ref "U7") (pin "21") (pinfunction "AC0_21") (pintype "bidirectional"))
    )
    (net (code "26") (name "FTDI_NSIWU") (class "Default")
      (node (ref "U1") (pin "K15") (pinfunction "IO_L44P_A3_M1DQ6_1_K15") (pintype "bidirectional"))
      (node (ref "U7") (pin "28") (pinfunction "AC4_28") (pintype "bidirectional"))
    )
    (net (code "27") (name "FTDI_NTXE") (class "Default")
      (node (ref "U1") (pin "M16") (pinfunction "IO_L46N_FOE_B_M1DQ3_1_M16") (pintype "bidirectional"))
      (node (ref "U7") (pin "25") (pinfunction "AC1_25") (pintype "bidirectional"))
    )
    (net (code "28") (name "FTDI_NWR") (class "Default")
      (node (ref "U1") (pin "L16") (pinfunction "IO_L47N_LDC_M1DQ1_1_L16") (pintype "bidirectional"))
      (node (ref "U7") (pin "27") (pinfunction "AC3_27") (pintype "bidirectional"))
    )
    (net (code "29") (name "GND") (class "Default")
      (node (ref "B1") (pin "P$2") (pinfunction "2_P$2") (pintype "bidirectional"))
      (node (ref "C10") (pin "P$2") (pinfunction "2_P$2") (pintype "passive"))
      (node (ref "C107") (pin "P$2") (pinfunction "2_P$2") (pintype "passive"))
      (node (ref "C11") (pin "P$1") (pinfunction "1_P$1") (pintype "passive"))
      (node (ref "C12") (pin "P$1") (pinfunction "1_P$1") (pintype "passive"))
      (node (ref "C13") (pin "P$1") (pinfunction "1_P$1") (pintype "passive"))
      (node (ref "C15") (pin "P$1") (pinfunction "1_P$1") (pintype "passive"))
      (node (ref "C17") (pin "P$2") (pinfunction "2_P$2") (pintype "passive"))
      (node (ref "C18") (pin "P$2") (pinfunction "2_P$2") (pintype "passive"))
      (node (ref "C19") (pin "P$2") (pinfunction "2_P$2") (pintype "passive"))
      (node (ref "C2") (pin "P$2") (pinfunction "2_P$2") (pintype "passive"))
      (node (ref "C21") (pin "P$2") (pinfunction "2_P$2") (pintype "bidirectional"))
      (node (ref "C22") (pin "P$2") (pinfunction "2_P$2") (pintype "passive"))
      (node (ref "C23") (pin "P$2") (pinfunction "2_P$2") (pintype "passive"))
      (node (ref "C24") (pin "P$2") (pinfunction "2_P$2") (pintype "bidirectional"))
      (node (ref "C25") (pin "P$2") (pinfunction "2_P$2") (pintype "bidirectional"))
      (node (ref "C26") (pin "P$2") (pinfunction "2_P$2") (pintype "bidirectional"))
      (node (ref "C27") (pin "P$2") (pinfunction "2_P$2") (pintype "passive"))
      (node (ref "C28") (pin "P$2") (pinfunction "2_P$2") (pintype "passive"))
      (node (ref "C29") (pin "P$2") (pinfunction "2_P$2") (pintype "passive"))
      (node (ref "C3") (pin "P$2") (pinfunction "2_P$2") (pintype "passive"))
      (node (ref "C30") (pin "P$2") (pinfunction "2_P$2") (pintype "passive"))
      (node (ref "C31") (pin "P$2") (pinfunction "2_P$2") (pintype "passive"))
      (node (ref "C32") (pin "P$2") (pinfunction "2_P$2") (pintype "passive"))
      (node (ref "C33") (pin "P$1") (pinfunction "1_P$1") (pintype "passive"))
      (node (ref "C34") (pin "P$2") (pinfunction "2_P$2") (pintype "passive"))
      (node (ref "C35") (pin "P$2") (pinfunction "2_P$2") (pintype "passive"))
      (node (ref "C36") (pin "P$1") (pinfunction "1_P$1") (pintype "passive"))
      (node (ref "C37") (pin "P$2") (pinfunction "2_P$2") (pintype "passive"))
      (node (ref "C38") (pin "P$2") (pinfunction "2_P$2") (pintype "passive"))
      (node (ref "C39") (pin "P$2") (pinfunction "2_P$2") (pintype "passive"))
      (node (ref "C4") (pin "P$2") (pinfunction "2_P$2") (pintype "passive"))
      (node (ref "C40") (pin "P$2") (pinfunction "2_P$2") (pintype "passive"))
      (node (ref "C41") (pin "P$1") (pinfunction "1_P$1") (pintype "passive"))
      (node (ref "C42") (pin "P$2") (pinfunction "2_P$2") (pintype "passive"))
      (node (ref "C43") (pin "P$2") (pinfunction "2_P$2") (pintype "passive"))
      (node (ref "C44") (pin "P$2") (pinfunction "2_P$2") (pintype "passive"))
      (node (ref "C45") (pin "2") (pinfunction "2_2") (pintype "passive"))
      (node (ref "C46") (pin "P$2") (pinfunction "2_P$2") (pintype "passive"))
      (node (ref "C47") (pin "P$1") (pinfunction "1_P$1") (pintype "passive"))
      (node (ref "C48") (pin "P$2") (pinfunction "2_P$2") (pintype "passive"))
      (node (ref "C49") (pin "P$2") (pinfunction "2_P$2") (pintype "passive"))
      (node (ref "C50") (pin "P$1") (pinfunction "1_P$1") (pintype "passive"))
      (node (ref "C51") (pin "P$1") (pinfunction "1_P$1") (pintype "passive"))
      (node (ref "C52") (pin "P$2") (pinfunction "2_P$2") (pintype "passive"))
      (node (ref "C53") (pin "P$2") (pinfunction "2_P$2") (pintype "passive"))
      (node (ref "C54") (pin "P$2") (pinfunction "2_P$2") (pintype "passive"))
      (node (ref "C55") (pin "P$2") (pinfunction "2_P$2") (pintype "passive"))
      (node (ref "C56") (pin "P$2") (pinfunction "2_P$2") (pintype "passive"))
      (node (ref "C57") (pin "P$1") (pinfunction "1_P$1") (pintype "passive"))
      (node (ref "C58") (pin "P$2") (pinfunction "2_P$2") (pintype "passive"))
      (node (ref "C59") (pin "P$1") (pinfunction "1_P$1") (pintype "passive"))
      (node (ref "C6") (pin "P$1") (pinfunction "1_P$1") (pintype "passive"))
      (node (ref "C60") (pin "P$2") (pinfunction "2_P$2") (pintype "passive"))
      (node (ref "C61") (pin "P$2") (pinfunction "2_P$2") (pintype "passive"))
      (node (ref "C62") (pin "P$2") (pinfunction "2_P$2") (pintype "passive"))
      (node (ref "C63") (pin "P$2") (pinfunction "2_P$2") (pintype "passive"))
      (node (ref "C64") (pin "P$2") (pinfunction "2_P$2") (pintype "passive"))
      (node (ref "C65") (pin "P$1") (pinfunction "1_P$1") (pintype "passive"))
      (node (ref "C66") (pin "P$2") (pinfunction "2_P$2") (pintype "passive"))
      (node (ref "C67") (pin "P$2") (pinfunction "2_P$2") (pintype "passive"))
      (node (ref "C68") (pin "P$2") (pinfunction "2_P$2") (pintype "passive"))
      (node (ref "C69") (pin "2") (pinfunction "2_2") (pintype "passive"))
      (node (ref "C7") (pin "P$1") (pinfunction "1_P$1") (pintype "passive"))
      (node (ref "C70") (pin "P$2") (pinfunction "2_P$2") (pintype "passive"))
      (node (ref "C71") (pin "P$2") (pinfunction "2_P$2") (pintype "passive"))
      (node (ref "C72") (pin "P$2") (pinfunction "2_P$2") (pintype "passive"))
      (node (ref "C73") (pin "P$2") (pinfunction "2_P$2") (pintype "passive"))
      (node (ref "C74") (pin "P$2") (pinfunction "2_P$2") (pintype "passive"))
      (node (ref "C75") (pin "P$2") (pinfunction "2_P$2") (pintype "passive"))
      (node (ref "C76") (pin "P$2") (pinfunction "2_P$2") (pintype "passive"))
      (node (ref "C77") (pin "P$2") (pinfunction "2_P$2") (pintype "passive"))
      (node (ref "C78") (pin "P$2") (pinfunction "2_P$2") (pintype "passive"))
      (node (ref "C8") (pin "P$2") (pinfunction "2_P$2") (pintype "passive"))
      (node (ref "C80") (pin "P$2") (pinfunction "2_P$2") (pintype "passive"))
      (node (ref "C81") (pin "P$2") (pinfunction "2_P$2") (pintype "passive"))
      (node (ref "C82") (pin "P$1") (pinfunction "1_P$1") (pintype "passive"))
      (node (ref "C86") (pin "P$2") (pinfunction "2_P$2") (pintype "bidirectional"))
      (node (ref "C87") (pin "P$2") (pinfunction "2_P$2") (pintype "bidirectional"))
      (node (ref "C9") (pin "P$2") (pinfunction "2_P$2") (pintype "passive"))
      (node (ref "C96") (pin "P$2") (pinfunction "2_P$2") (pintype "passive"))
      (node (ref "H2") (pin "B3,0") (pinfunction "MOUNT_B3,0") (pintype "passive"))
      (node (ref "H3") (pin "B3,0") (pinfunction "MOUNT_B3,0") (pintype "passive"))
      (node (ref "H4") (pin "B3,0") (pinfunction "MOUNT_B3,0") (pintype "passive"))
      (node (ref "H5") (pin "B3,0") (pinfunction "MOUNT_B3,0") (pintype "passive"))
      (node (ref "J1") (pin "P2") (pinfunction "2_P2") (pintype "power_in"))
      (node (ref "J1") (pin "P3") (pinfunction "3_P3") (pintype "power_in"))
      (node (ref "J1") (pin "P4") (pinfunction "4_P4") (pintype "power_in"))
      (node (ref "J1") (pin "P5") (pinfunction "5_P5") (pintype "power_in"))
      (node (ref "J6") (pin "PIN_5") (pinfunction "5_PIN_5") (pintype "input"))
      (node (ref "L5") (pin "P$1") (pinfunction "1_P$1") (pintype "passive"))
      (node (ref "Q1") (pin "1") (pinfunction "G_1") (pintype "passive"))
      (node (ref "R14") (pin "P$2") (pinfunction "2_P$2") (pintype "passive"))
      (node (ref "R18") (pin "P$1") (pinfunction "1_P$1") (pintype "passive"))
      (node (ref "R20") (pin "P$1") (pinfunction "1_P$1") (pintype "passive"))
      (node (ref "R62") (pin "P$2") (pinfunction "2_P$2") (pintype "passive"))
      (node (ref "R63") (pin "P$2") (pinfunction "2_P$2") (pintype "passive"))
      (node (ref "R7") (pin "P$2") (pinfunction "2_P$2") (pintype "passive"))
      (node (ref "R8") (pin "P$1") (pinfunction "1_P$1") (pintype "passive"))
      (node (ref "SHLD2") (pin "1") (pinfunction "P$1_1") (pintype "power_in"))
      (node (ref "SHLD2") (pin "10") (pinfunction "P$10_10") (pintype "power_in"))
      (node (ref "SHLD2") (pin "11") (pinfunction "P$11_11") (pintype "power_in"))
      (node (ref "SHLD2") (pin "12") (pinfunction "P$12_12") (pintype "power_in"))
      (node (ref "SHLD2") (pin "13") (pinfunction "P$13_13") (pintype "power_in"))
      (node (ref "SHLD2") (pin "14") (pinfunction "P$14_14") (pintype "power_in"))
      (node (ref "SHLD2") (pin "15") (pinfunction "P$15_15") (pintype "power_in"))
      (node (ref "SHLD2") (pin "16") (pinfunction "P$16_16") (pintype "power_in"))
      (node (ref "SHLD2") (pin "17") (pinfunction "P$17_17") (pintype "power_in"))
      (node (ref "SHLD2") (pin "18") (pinfunction "P$18_18") (pintype "power_in"))
      (node (ref "SHLD2") (pin "19") (pinfunction "P$19_19") (pintype "power_in"))
      (node (ref "SHLD2") (pin "2") (pinfunction "P$2_2") (pintype "power_in"))
      (node (ref "SHLD2") (pin "20") (pinfunction "P$20_20") (pintype "power_in"))
      (node (ref "SHLD2") (pin "21") (pinfunction "P$21_21") (pintype "power_in"))
      (node (ref "SHLD2") (pin "22") (pinfunction "P$22_22") (pintype "power_in"))
      (node (ref "SHLD2") (pin "23") (pinfunction "P$23_23") (pintype "power_in"))
      (node (ref "SHLD2") (pin "24") (pinfunction "P$24_24") (pintype "power_in"))
      (node (ref "SHLD2") (pin "25") (pinfunction "P$25_25") (pintype "power_in"))
      (node (ref "SHLD2") (pin "26") (pinfunction "P$26_26") (pintype "power_in"))
      (node (ref "SHLD2") (pin "27") (pinfunction "P$27_27") (pintype "power_in"))
      (node (ref "SHLD2") (pin "28") (pinfunction "P$28_28") (pintype "power_in"))
      (node (ref "SHLD2") (pin "3") (pinfunction "P$3_3") (pintype "power_in"))
      (node (ref "SHLD2") (pin "4") (pinfunction "P$4_4") (pintype "power_in"))
      (node (ref "SHLD2") (pin "5") (pinfunction "P$5_5") (pintype "power_in"))
      (node (ref "SHLD2") (pin "6") (pinfunction "P$6_6") (pintype "power_in"))
      (node (ref "SHLD2") (pin "7") (pinfunction "P$7_7") (pintype "power_in"))
      (node (ref "SHLD2") (pin "8") (pinfunction "P$8_8") (pintype "power_in"))
      (node (ref "SHLD2") (pin "9") (pinfunction "P$9_9") (pintype "power_in"))
      (node (ref "U1") (pin "A1") (pinfunction "GND_A1") (pintype "power_in"))
      (node (ref "U1") (pin "A16") (pinfunction "GND_A16") (pintype "power_in"))
      (node (ref "U1") (pin "B11") (pinfunction "GND_B11") (pintype "power_in"))
      (node (ref "U1") (pin "B7") (pinfunction "GND_B7") (pintype "power_in"))
      (node (ref "U1") (pin "D13") (pinfunction "GND_D13") (pintype "power_in"))
      (node (ref "U1") (pin "D4") (pinfunction "GND_D4") (pintype "power_in"))
      (node (ref "U1") (pin "E9") (pinfunction "GND_E9") (pintype "power_in"))
      (node (ref "U1") (pin "G15") (pinfunction "GND_G15") (pintype "power_in"))
      (node (ref "U1") (pin "G2") (pinfunction "GND_G2") (pintype "power_in"))
      (node (ref "U1") (pin "G8") (pinfunction "GND_G8") (pintype "power_in"))
      (node (ref "U1") (pin "H12") (pinfunction "GND_H12") (pintype "power_in"))
      (node (ref "U1") (pin "H7") (pinfunction "GND_H7") (pintype "power_in"))
      (node (ref "U1") (pin "H9") (pinfunction "GND_H9") (pintype "power_in"))
      (node (ref "U1") (pin "J5") (pinfunction "GND_J5") (pintype "power_in"))
      (node (ref "U1") (pin "J8") (pinfunction "GND_J8") (pintype "power_in"))
      (node (ref "U1") (pin "K7") (pinfunction "GND_K7") (pintype "power_in"))
      (node (ref "U1") (pin "K9") (pinfunction "GND_K9") (pintype "power_in"))
      (node (ref "U1") (pin "L15") (pinfunction "GND_L15") (pintype "power_in"))
      (node (ref "U1") (pin "L2") (pinfunction "GND_L2") (pintype "power_in"))
      (node (ref "U1") (pin "M8") (pinfunction "GND_M8") (pintype "power_in"))
      (node (ref "U1") (pin "N11") (pinfunction "IO_L13P_M1_2_N11") (pintype "bidirectional"))
      (node (ref "U1") (pin "N13") (pinfunction "GND_N13") (pintype "power_in"))
      (node (ref "U1") (pin "P3") (pinfunction "GND_P3") (pintype "power_in"))
      (node (ref "U1") (pin "R10") (pinfunction "GND_R10") (pintype "power_in"))
      (node (ref "U1") (pin "R6") (pinfunction "GND_R6") (pintype "power_in"))
      (node (ref "U1") (pin "T1") (pinfunction "GND_T1") (pintype "power_in"))
      (node (ref "U1") (pin "T16") (pinfunction "GND_T16") (pintype "power_in"))
      (node (ref "U10") (pin "29") (pinfunction "EPGND_29") (pintype "bidirectional"))
      (node (ref "U12") (pin "2") (pinfunction "GND_2") (pintype "bidirectional"))
      (node (ref "U13") (pin "4") (pinfunction "GND_4") (pintype "power_in"))
      (node (ref "U13") (pin "9") (pinfunction "EP_9") (pintype "power_in"))
      (node (ref "U2") (pin "11") (pinfunction "GND2_11") (pintype "bidirectional"))
      (node (ref "U2") (pin "5") (pinfunction "GND1_5") (pintype "bidirectional"))
      (node (ref "U3") (pin "12") (pinfunction "VSSA_12") (pintype "power_in"))
      (node (ref "U3") (pin "18") (pinfunction "VSS4_18") (pintype "bidirectional"))
      (node (ref "U3") (pin "60") (pinfunction "BOOT0_60") (pintype "input"))
      (node (ref "U3") (pin "63") (pinfunction "VSS3_63") (pintype "power_in"))
      (node (ref "U4") (pin "1") (pinfunction "GND1_1") (pintype "bidirectional"))
      (node (ref "U4") (pin "2") (pinfunction "GND2_2") (pintype "bidirectional"))
      (node (ref "U5") (pin "2") (pinfunction "2_2") (pintype "power_in"))
      (node (ref "U5") (pin "3") (pinfunction "3_3") (pintype "power_in"))
      (node (ref "U5") (pin "4") (pinfunction "4_4") (pintype "power_in"))
      (node (ref "U5") (pin "5") (pinfunction "5_5") (pintype "power_in"))
      (node (ref "U6") (pin "2") (pinfunction "VSS_2") (pintype "power_in"))
      (node (ref "U7") (pin "10") (pinfunction "GND1_10") (pintype "power_in"))
      (node (ref "U7") (pin "11") (pinfunction "GND2_11") (pintype "power_in"))
      (node (ref "U7") (pin "22") (pinfunction "GND3_22") (pintype "power_in"))
      (node (ref "U7") (pin "23") (pinfunction "GND4_23") (pintype "power_in"))
      (node (ref "U7") (pin "35") (pinfunction "GND5_35") (pintype "power_in"))
      (node (ref "U7") (pin "36") (pinfunction "GND6_36") (pintype "power_in"))
      (node (ref "U7") (pin "4") (pinfunction "AGND1_4") (pintype "power_in"))
      (node (ref "U7") (pin "41") (pinfunction "AGND3_41") (pintype "power_in"))
      (node (ref "U7") (pin "42") (pinfunction "TEST_42") (pintype "input"))
      (node (ref "U7") (pin "47") (pinfunction "GND7_47") (pintype "power_in"))
      (node (ref "U7") (pin "48") (pinfunction "GND8_48") (pintype "power_in"))
      (node (ref "U7") (pin "49") (pinfunction "EPGND_49") (pintype "power_in"))
      (node (ref "U7") (pin "9") (pinfunction "AGND2_9") (pintype "power_in"))
      (node (ref "U8") (pin "2") (pinfunction "GND1_2") (pintype "power_in"))
      (node (ref "U8") (pin "3") (pinfunction "GND2_3") (pintype "power_in"))
      (node (ref "U8") (pin "5") (pinfunction "GND3_5") (pintype "power_in"))
      (node (ref "U9") (pin "3") (pinfunction "VSS_3") (pintype "bidirectional"))
      (node (ref "X1") (pin "1") (pinfunction "1_1") (pintype "bidirectional"))
      (node (ref "X3") (pin "1") (pinfunction "1_1") (pintype "bidirectional"))
      (node (ref "X5") (pin "3") (pinfunction "3_3") (pintype "bidirectional"))
      (node (ref "X5") (pin "5") (pinfunction "5_5") (pintype "bidirectional"))
      (node (ref "X5") (pin "7") (pinfunction "7_7") (pintype "bidirectional"))
      (node (ref "X5") (pin "9") (pinfunction "9_9") (pintype "bidirectional"))
      (node (ref "X6") (pin "1") (pinfunction "1_1") (pintype "bidirectional"))
    )
    (net (code "30") (name "JTAG_RST") (class "Default")
      (node (ref "B1") (pin "P$1") (pinfunction "1_P$1") (pintype "bidirectional"))
      (node (ref "C32") (pin "P$1") (pinfunction "1_P$1") (pintype "passive"))
      (node (ref "R34") (pin "P$1") (pinfunction "1_P$1") (pintype "passive"))
      (node (ref "U3") (pin "7") (pinfunction "NRST_7") (pintype "bidirectional"))
      (node (ref "X5") (pin "10") (pinfunction "10_10") (pintype "bidirectional"))
    )
    (net (code "31") (name "JTAG_TCK") (class "Default")
      (node (ref "U1") (pin "C14") (pinfunction "TCK_C14") (pintype "input"))
      (node (ref "U3") (pin "49") (pinfunction "PA14/JTCK/SWCLK_49") (pintype "bidirectional"))
      (node (ref "X5") (pin "4") (pinfunction "4_4") (pintype "bidirectional"))
    )
    (net (code "32") (name "JTAG_TDI") (class "Default")
      (node (ref "U1") (pin "C12") (pinfunction "TDI_C12") (pintype "input"))
      (node (ref "X5") (pin "8") (pinfunction "8_8") (pintype "bidirectional"))
    )
    (net (code "33") (name "JTAG_TDO") (class "Default")
      (node (ref "U3") (pin "55") (pinfunction "PB3/JTDO--TIM2CH2/TRACESWO/SPI1SCK_55") (pintype "bidirectional"))
      (node (ref "X5") (pin "6") (pinfunction "6_6") (pintype "bidirectional"))
    )
    (net (code "34") (name "JTAG_TMS") (class "Default")
      (node (ref "U1") (pin "A15") (pinfunction "TMS_A15") (pintype "input"))
      (node (ref "U3") (pin "46") (pinfunction "PA13/JTMS/SWDIO_46") (pintype "bidirectional"))
      (node (ref "X5") (pin "2") (pinfunction "2_2") (pintype "bidirectional"))
    )
    (net (code "35") (name "MAX_ANT_FLAG") (class "Default")
      (node (ref "U10") (pin "1") (pinfunction "ANT_FLAG_1") (pintype "bidirectional"))
      (node (ref "U3") (pin "25") (pinfunction "PC5-ADC15_25") (pintype "bidirectional"))
    )
    (net (code "36") (name "MAX_CLKOUT") (class "Default")
      (node (ref "U1") (pin "J14") (pinfunction "IO_L43P_GCLK5_M1DQ4_1_J14") (pintype "bidirectional"))
      (node (ref "U10") (pin "16") (pinfunction "CLK_OUT_16") (pintype "bidirectional"))
    )
    (net (code "37") (name "MAX_I0") (class "Default")
      (node (ref "U1") (pin "E16") (pinfunction "IO_L34N_A12_M1BA2_1_E16") (pintype "bidirectional"))
      (node (ref "U10") (pin "20") (pinfunction "I0_20") (pintype "bidirectional"))
    )
    (net (code "38") (name "MAX_I1") (class "Default")
      (node (ref "U1") (pin "E15") (pinfunction "IO_L34P_A13_M1WE_1_E15") (pintype "bidirectional"))
      (node (ref "U10") (pin "21") (pinfunction "I1_21") (pintype "bidirectional"))
    )
    (net (code "39") (name "MAX_LD") (class "Default")
      (node (ref "U10") (pin "6") (pinfunction "LD_6") (pintype "bidirectional"))
      (node (ref "U3") (pin "41") (pinfunction "PA8-USART1CK/MCO/TIM1CH1_41") (pintype "bidirectional"))
    )
    (net (code "40") (name "MAX_NIDLE") (class "Default")
      (node (ref "R12") (pin "P$1") (pinfunction "1_P$1") (pintype "passive"))
      (node (ref "U10") (pin "24") (pinfunction "~{IDLE}_24") (pintype "bidirectional"))
      (node (ref "U3") (pin "29") (pinfunction "PB10-I2C2SCL/USART3TX-TIM2CH3_29") (pintype "bidirectional"))
    )
    (net (code "41") (name "MAX_NSHDN") (class "Default")
      (node (ref "R19") (pin "P$1") (pinfunction "1_P$1") (pintype "passive"))
      (node (ref "U10") (pin "7") (pinfunction "~{SHDN}_7") (pintype "bidirectional"))
      (node (ref "U3") (pin "62") (pinfunction "PB9-TIM4CH4-I2C1SDA/CANTX_62") (pintype "bidirectional"))
    )
    (net (code "42") (name "MAX_PGM") (class "Default")
      (node (ref "R20") (pin "P$2") (pinfunction "2_P$2") (pintype "passive"))
      (node (ref "U10") (pin "26") (pinfunction "PGM_26") (pintype "bidirectional"))
      (node (ref "U3") (pin "61") (pinfunction "PB8-TIM4CH3-I2C1SCL/CANRX_61") (pintype "bidirectional"))
    )
    (net (code "43") (name "MAX_Q0") (class "Default")
      (node (ref "U1") (pin "F15") (pinfunction "IO_L35P_A11_M1A7_1_F15") (pintype "bidirectional"))
      (node (ref "U10") (pin "18") (pinfunction "Q0_18") (pintype "bidirectional"))
    )
    (net (code "44") (name "MAX_Q1") (class "Default")
      (node (ref "U1") (pin "F16") (pinfunction "IO_L35N_A10_M1A2_1_F16") (pintype "bidirectional"))
      (node (ref "U10") (pin "17") (pinfunction "Q1_17") (pintype "bidirectional"))
    )
    (net (code "45") (name "Net-(C1-1)") (class "Default")
      (node (ref "C1") (pin "P$1") (pinfunction "1_P$1") (pintype "passive"))
      (node (ref "R61") (pin "P$1") (pinfunction "1_P$1") (pintype "passive"))
      (node (ref "R62") (pin "P$1") (pinfunction "1_P$1") (pintype "passive"))
      (node (ref "U2") (pin "1") (pinfunction "VFB1_1") (pintype "bidirectional"))
    )
    (net (code "46") (name "Net-(C5-2)") (class "Default")
      (node (ref "C5") (pin "P$2") (pinfunction "2_P$2") (pintype "passive"))
      (node (ref "R63") (pin "P$1") (pinfunction "1_P$1") (pintype "passive"))
      (node (ref "R64") (pin "P$1") (pinfunction "1_P$1") (pintype "passive"))
      (node (ref "U2") (pin "10") (pinfunction "VFB2_10") (pintype "bidirectional"))
    )
    (net (code "47") (name "Net-(C7-2)") (class "Default")
      (node (ref "C7") (pin "P$2") (pinfunction "2_P$2") (pintype "passive"))
      (node (ref "C9") (pin "P$1") (pinfunction "1_P$1") (pintype "passive"))
      (node (ref "R65") (pin "P$2") (pinfunction "2_P$2") (pintype "passive"))
      (node (ref "U12") (pin "1") (pinfunction "VIN_1") (pintype "bidirectional"))
      (node (ref "U12") (pin "3") (pinfunction "EN_3") (pintype "bidirectional"))
    )
    (net (code "48") (name "Net-(C12-2)") (class "Default")
      (node (ref "C12") (pin "P$2") (pinfunction "2_P$2") (pintype "passive"))
      (node (ref "C13") (pin "P$2") (pinfunction "2_P$2") (pintype "passive"))
      (node (ref "C36") (pin "P$2") (pinfunction "2_P$2") (pintype "passive"))
      (node (ref "C41") (pin "P$2") (pinfunction "2_P$2") (pintype "passive"))
      (node (ref "L1") (pin "P$1") (pinfunction "1_P$1") (pintype "passive"))
      (node (ref "L3") (pin "P$2") (pinfunction "2_P$2") (pintype "passive"))
      (node (ref "U10") (pin "3") (pinfunction "ANT_BIAS_3") (pintype "bidirectional"))
    )
    (net (code "49") (name "Net-(C14-1)") (class "Default")
      (node (ref "C14") (pin "P$1") (pinfunction "1_P$1") (pintype "passive"))
      (node (ref "J1") (pin "P1") (pinfunction "1_P1") (pintype "bidirectional"))
      (node (ref "L3") (pin "P$1") (pinfunction "1_P$1") (pintype "passive"))
    )
    (net (code "50") (name "Net-(C14-2)") (class "Default")
      (node (ref "C14") (pin "P$2") (pinfunction "2_P$2") (pintype "passive"))
      (node (ref "U10") (pin "25") (pinfunction "LNA_IN2_25") (pintype "bidirectional"))
    )
    (net (code "51") (name "Net-(C15-2)") (class "Default")
      (node (ref "C15") (pin "P$2") (pinfunction "2_P$2") (pintype "passive"))
      (node (ref "C47") (pin "P$2") (pinfunction "2_P$2") (pintype "passive"))
      (node (ref "R11") (pin "P$1") (pinfunction "1_P$1") (pintype "passive"))
      (node (ref "U9") (pin "1") (pinfunction "VDD_1") (pintype "bidirectional"))
    )
    (net (code "52") (name "Net-(C16-1)") (class "Default")
      (node (ref "C16") (pin "P$1") (pinfunction "1_P$1") (pintype "passive"))
      (node (ref "L1") (pin "P$2") (pinfunction "2_P$2") (pintype "passive"))
      (node (ref "U5") (pin "1") (pinfunction "1_1") (pintype "bidirectional"))
    )
    (net (code "53") (name "Net-(C16-2)") (class "Default")
      (node (ref "C16") (pin "P$2") (pinfunction "2_P$2") (pintype "passive"))
      (node (ref "L4") (pin "P$1") (pinfunction "1_P$1") (pintype "passive"))
      (node (ref "L5") (pin "P$2") (pinfunction "2_P$2") (pintype "passive"))
    )
    (net (code "54") (name "Net-(C18-1)") (class "Default")
      (node (ref "C18") (pin "P$1") (pinfunction "1_P$1") (pintype "passive"))
      (node (ref "R2") (pin "P$1") (pinfunction "1_P$1") (pintype "passive"))
    )
    (net (code "55") (name "Net-(C19-1)") (class "Default")
      (node (ref "C19") (pin "P$1") (pinfunction "1_P$1") (pintype "passive"))
      (node (ref "R2") (pin "P$2") (pinfunction "2_P$2") (pintype "passive"))
      (node (ref "U10") (pin "12") (pinfunction "CP_OUT_12") (pintype "bidirectional"))
    )
    (net (code "56") (name "Net-(C20-1)") (class "Default")
      (node (ref "C20") (pin "P$1") (pinfunction "1_P$1") (pintype "passive"))
      (node (ref "U10") (pin "15") (pinfunction "XTAL_15") (pintype "bidirectional"))
    )
    (net (code "57") (name "Net-(C20-2)") (class "Default")
      (node (ref "C20") (pin "P$2") (pinfunction "2_P$2") (pintype "passive"))
      (node (ref "U4") (pin "3") (pinfunction "OUT_3") (pintype "bidirectional"))
    )
    (net (code "58") (name "Net-(C34-1)") (class "Default")
      (node (ref "C34") (pin "P$1") (pinfunction "1_P$1") (pintype "passive"))
      (node (ref "U7") (pin "2") (pinfunction "XCSO_2") (pintype "output"))
      (node (ref "X4") (pin "2") (pinfunction "2_2") (pintype "bidirectional"))
    )
    (net (code "59") (name "Net-(C35-1)") (class "Default")
      (node (ref "C35") (pin "P$1") (pinfunction "1_P$1") (pintype "passive"))
      (node (ref "U7") (pin "1") (pinfunction "XCSI_1") (pintype "input"))
      (node (ref "X4") (pin "1") (pinfunction "1_1") (pintype "bidirectional"))
    )
    (net (code "60") (name "Net-(C38-1)") (class "Default")
      (node (ref "C38") (pin "P$1") (pinfunction "1_P$1") (pintype "passive"))
      (node (ref "L2") (pin "P$1") (pinfunction "1_P$1") (pintype "passive"))
      (node (ref "U10") (pin "4") (pinfunction "VCCRF_4") (pintype "bidirectional"))
    )
    (net (code "61") (name "Net-(C49-1)") (class "Default")
      (node (ref "C49") (pin "P$1") (pinfunction "1_P$1") (pintype "passive"))
      (node (ref "U7") (pin "38") (pinfunction "VCCCORE_38") (pintype "output"))
    )
    (net (code "62") (name "Net-(C59-2)") (class "Default")
      (node (ref "C59") (pin "P$2") (pinfunction "2_P$2") (pintype "passive"))
      (node (ref "C64") (pin "P$1") (pinfunction "1_P$1") (pintype "passive"))
      (node (ref "L10") (pin "P$2") (pinfunction "2_P$2") (pintype "passive"))
      (node (ref "U7") (pin "3") (pinfunction "VPHY_3") (pintype "power_in"))
    )
    (net (code "63") (name "Net-(C65-2)") (class "Default")
      (node (ref "C65") (pin "P$2") (pinfunction "2_P$2") (pintype "passive"))
      (node (ref "C68") (pin "P$1") (pinfunction "1_P$1") (pintype "passive"))
      (node (ref "L11") (pin "P$2") (pinfunction "2_P$2") (pintype "passive"))
      (node (ref "U7") (pin "8") (pinfunction "VPLL_8") (pintype "power_in"))
    )
    (net (code "64") (name "Net-(C66-1)") (class "Default")
      (node (ref "C66") (pin "P$1") (pinfunction "1_P$1") (pintype "passive"))
      (node (ref "U3") (pin "31") (pinfunction "VSS1_31") (pintype "power_in"))
    )
    (net (code "65") (name "Net-(C75-1)") (class "Default")
      (node (ref "C75") (pin "P$1") (pinfunction "1_P$1") (pintype "passive"))
      (node (ref "U7") (pin "37") (pinfunction "VCCA_37") (pintype "output"))
    )
    (net (code "66") (name "Net-(C82-2)") (class "Default")
      (node (ref "C82") (pin "P$2") (pinfunction "2_P$2") (pintype "passive"))
      (node (ref "U3") (pin "47") (pinfunction "VSS2_47") (pintype "power_in"))
    )
    (net (code "67") (name "Net-(C95-1)") (class "Default")
      (node (ref "C95") (pin "P$1") (pinfunction "1_P$1") (pintype "passive"))
      (node (ref "U9") (pin "2") (pinfunction "RFOUT_2") (pintype "bidirectional"))
    )
    (net (code "68") (name "Net-(C95-2)") (class "Default")
      (node (ref "C95") (pin "P$2") (pinfunction "2_P$2") (pintype "passive"))
      (node (ref "U10") (pin "27") (pinfunction "LNA_IN1_27") (pintype "bidirectional"))
    )
    (net (code "69") (name "Net-(L4-2)") (class "Default")
      (node (ref "L4") (pin "P$2") (pinfunction "2_P$2") (pintype "passive"))
      (node (ref "U9") (pin "4") (pinfunction "RFIN_4") (pintype "bidirectional"))
    )
    (net (code "70") (name "Net-(R1-1)") (class "Default")
      (node (ref "R1") (pin "P$1") (pinfunction "1_P$1") (pintype "passive"))
      (node (ref "U2") (pin "8") (pinfunction "NPOR_8") (pintype "bidirectional"))
    )
    (net (code "71") (name "Net-(R3-1)") (class "Default")
      (node (ref "R3") (pin "P$1") (pinfunction "1_P$1") (pintype "passive"))
      (node (ref "R6") (pin "P$2") (pinfunction "2_P$2") (pintype "passive"))
      (node (ref "U6") (pin "3") (pinfunction "DI_3") (pintype "input"))
      (node (ref "U7") (pin "43") (pinfunction "EEDATA_43") (pintype "bidirectional"))
    )
    (net (code "72") (name "Net-(R3-2)") (class "Default")
      (node (ref "R3") (pin "P$2") (pinfunction "2_P$2") (pintype "passive"))
      (node (ref "U6") (pin "1") (pinfunction "DO_1") (pintype "output"))
    )
    (net (code "73") (name "Net-(R4-2)") (class "Default")
      (node (ref "R4") (pin "P$2") (pinfunction "2_P$2") (pintype "passive"))
      (node (ref "U6") (pin "5") (pinfunction "CS_5") (pintype "input"))
      (node (ref "U7") (pin "45") (pinfunction "EECS_45") (pintype "bidirectional"))
    )
    (net (code "74") (name "Net-(R5-2)") (class "Default")
      (node (ref "R5") (pin "P$2") (pinfunction "2_P$2") (pintype "passive"))
      (node (ref "U6") (pin "4") (pinfunction "CLK_4") (pintype "input"))
      (node (ref "U7") (pin "44") (pinfunction "EECLK_44") (pintype "output"))
    )
    (net (code "75") (name "Net-(R7-1)") (class "Default")
      (node (ref "R7") (pin "P$1") (pinfunction "1_P$1") (pintype "passive"))
      (node (ref "U7") (pin "5") (pinfunction "REF_5") (pintype "input"))
    )
    (net (code "76") (name "Net-(R9-2)") (class "Default")
      (node (ref "R9") (pin "P$2") (pinfunction "2_P$2") (pintype "passive"))
      (node (ref "U7") (pin "31") (pinfunction "AC7_31") (pintype "bidirectional"))
    )
    (net (code "77") (name "Net-(R10-1)") (class "Default")
      (node (ref "R10") (pin "P$1") (pinfunction "1_P$1") (pintype "passive"))
      (node (ref "U3") (pin "26") (pinfunction "PB0-ADC8/TIM3CH3-TIM1CH2N_26") (pintype "bidirectional"))
    )
    (net (code "78") (name "Net-(R14-1)") (class "Default")
      (node (ref "R14") (pin "P$1") (pinfunction "1_P$1") (pintype "passive"))
      (node (ref "U1") (pin "P14") (pinfunction "SUSPEND_P14") (pintype "input"))
    )
    (net (code "79") (name "Net-(R18-2)") (class "Default")
      (node (ref "R18") (pin "P$2") (pinfunction "2_P$2") (pintype "passive"))
      (node (ref "U1") (pin "C4") (pinfunction "IO_L1P_HSWAPEN_0_C4") (pintype "bidirectional"))
    )
    (net (code "80") (name "Net-(R28-2)") (class "Default")
      (node (ref "LED2") (pin "A") (pinfunction "A_A") (pintype "passive"))
      (node (ref "R28") (pin "P$2") (pinfunction "2_P$2") (pintype "passive"))
    )
    (net (code "81") (name "Net-(R30-1)") (class "Default")
      (node (ref "LED1") (pin "A") (pinfunction "A_A") (pintype "passive"))
      (node (ref "R30") (pin "P$1") (pinfunction "1_P$1") (pintype "passive"))
    )
    (net (code "82") (name "Net-(U2-SW1)") (class "Default")
      (node (ref "L13") (pin "2") (pinfunction "2_2") (pintype "bidirectional"))
      (node (ref "U2") (pin "4") (pinfunction "SW1_4") (pintype "bidirectional"))
    )
    (net (code "83") (name "Net-(U2-SW2)") (class "Default")
      (node (ref "L14") (pin "1") (pinfunction "1_1") (pintype "bidirectional"))
      (node (ref "U2") (pin "7") (pinfunction "SW2_7") (pintype "bidirectional"))
    )
    (net (code "84") (name "Net-(U3-PC3-ADC13)") (class "Default")
      (node (ref "LED2") (pin "C") (pinfunction "C_C") (pintype "passive"))
      (node (ref "U3") (pin "11") (pinfunction "PC3-ADC13_11") (pintype "bidirectional"))
    )
    (net (code "85") (name "Net-(U3-PC4-ADC14)") (class "Default")
      (node (ref "LED1") (pin "C") (pinfunction "C_C") (pintype "passive"))
      (node (ref "U3") (pin "24") (pinfunction "PC4-ADC14_24") (pintype "bidirectional"))
    )
    (net (code "86") (name "Net-(U10A-LNA_OUT)") (class "Default")
      (node (ref "U10") (pin "2") (pinfunction "LNA_OUT_2") (pintype "bidirectional"))
      (node (ref "U8") (pin "1") (pinfunction "RFIN_1") (pintype "bidirectional"))
    )
    (net (code "87") (name "Net-(U10A-MIX_IN)") (class "Default")
      (node (ref "U10") (pin "5") (pinfunction "MIX_IN_5") (pintype "bidirectional"))
      (node (ref "U8") (pin "4") (pinfunction "RFOUT_4") (pintype "bidirectional"))
    )
    (net (code "88") (name "SPI1MISO") (class "Default")
      (node (ref "U1") (pin "A12") (pinfunction "IO_L62N_VREF_0_A12") (pintype "bidirectional"))
      (node (ref "U3") (pin "22") (pinfunction "PA6-SPI1MISO/ADC6/TIM3CH1-TIM1BKIN_22") (pintype "bidirectional"))
    )
    (net (code "89") (name "SPI1MOSI") (class "Default")
      (node (ref "U1") (pin "C11") (pinfunction "IO_L39P_0_C11") (pintype "bidirectional"))
      (node (ref "U3") (pin "23") (pinfunction "PA7-SPI1MOSI/ADC7/TIM3CH2-TIM1CH1N_23") (pintype "bidirectional"))
    )
    (net (code "90") (name "SPI1NSS") (class "Default")
      (node (ref "U1") (pin "A10") (pinfunction "IO_L35N_GCLK16_0_A10") (pintype "bidirectional"))
      (node (ref "U3") (pin "20") (pinfunction "PA4-SPI1NSS/ADC4/USART2CK_20") (pintype "bidirectional"))
    )
    (net (code "91") (name "SPI1SCK") (class "Default")
      (node (ref "U1") (pin "B10") (pinfunction "IO_L35P_GCLK17_0_B10") (pintype "bidirectional"))
      (node (ref "U3") (pin "21") (pinfunction "PA5-SPI1SCK/ADC5_21") (pintype "bidirectional"))
    )
    (net (code "92") (name "SPI2MISO") (class "Default")
      (node (ref "U1") (pin "P10") (pinfunction "IO_L3P_D0_DIN_MISO_MISO1_2_P10") (pintype "bidirectional"))
      (node (ref "U13") (pin "2") (pinfunction "DO_2") (pintype "bidirectional"))
      (node (ref "U3") (pin "35") (pinfunction "PB14-SPI2MISO/USART3RTS/TIM1CH2N_35") (pintype "bidirectional"))
    )
    (net (code "93") (name "SPI2MOSI") (class "Default")
      (node (ref "U1") (pin "T10") (pinfunction "IO_L3N_MOSI_CSI_B_MISO0_2_T10") (pintype "bidirectional"))
      (node (ref "U10") (pin "8") (pinfunction "SDATA_8") (pintype "bidirectional"))
      (node (ref "U13") (pin "5") (pinfunction "DI_5") (pintype "bidirectional"))
      (node (ref "U3") (pin "36") (pinfunction "PB15-SPI2MOSI/TIM1CH3N_36") (pintype "bidirectional"))
    )
    (net (code "94") (name "SPI2NSS_FLASH") (class "Default")
      (node (ref "R13") (pin "P$1") (pinfunction "1_P$1") (pintype "passive"))
      (node (ref "U1") (pin "T3") (pinfunction "IO_L65N_CSO_B_2_T3") (pintype "bidirectional"))
      (node (ref "U13") (pin "1") (pinfunction "NCS_1") (pintype "input"))
      (node (ref "U3") (pin "33") (pinfunction "PB12-SPI2NSS/I2C2SMBAI/USART3CK/TIM1BKIN_33") (pintype "bidirectional"))
    )
    (net (code "95") (name "SPI2NSS_FPGA") (class "Default")
      (node (ref "U3") (pin "10") (pinfunction "PC2-ADC12_10") (pintype "bidirectional"))
    )
    (net (code "96") (name "SPI2NSS_MAX") (class "Default")
      (node (ref "U10") (pin "10") (pinfunction "~{CS}_10") (pintype "bidirectional"))
      (node (ref "U3") (pin "30") (pinfunction "PB11-I2C2SDA/USART3RX-TIM2CH4_30") (pintype "bidirectional"))
    )
    (net (code "97") (name "SPI2SCK") (class "Default")
      (node (ref "U1") (pin "R11") (pinfunction "IO_L1P_CCLK_2_R11") (pintype "bidirectional"))
      (node (ref "U10") (pin "9") (pinfunction "SCLK_9") (pintype "bidirectional"))
      (node (ref "U13") (pin "6") (pinfunction "CLK_6") (pintype "input"))
      (node (ref "U3") (pin "34") (pinfunction "PB13-SPI2SCK/USART3CTS/TIM1CH1N_34") (pintype "bidirectional"))
    )
    (net (code "98") (name "STM_CLK_IN") (class "Default")
      (node (ref "U1") (pin "P9") (pinfunction "IO_L14N_D12_2_P9") (pintype "bidirectional"))
      (node (ref "U3") (pin "5") (pinfunction "PD0-OSC_IN-CANRX_5") (pintype "input"))
    )
    (net (code "99") (name "TIM2CH1ETR") (class "Default")
      (node (ref "U1") (pin "C10") (pinfunction "IO_L37N_GCLK12_0_C10") (pintype "bidirectional"))
      (node (ref "U3") (pin "14") (pinfunction "PA0-WKUP/USART2CTS/ADC0/TIM2CH1ETR_14") (pintype "bidirectional"))
    )
    (net (code "100") (name "TIM2CH2") (class "Default")
      (node (ref "U1") (pin "A9") (pinfunction "IO_L34N_GCLK18_0_A9") (pintype "bidirectional"))
      (node (ref "U3") (pin "15") (pinfunction "PA1-USART2RTS/ADC1/TIM2CH2_15") (pintype "bidirectional"))
    )
    (net (code "101") (name "TIM2CH3") (class "Default")
      (node (ref "U1") (pin "A7") (pinfunction "IO_L6N_0_A7") (pintype "bidirectional"))
      (node (ref "U3") (pin "16") (pinfunction "PA2-USART2TX/ADC2/TIM2CH3_16") (pintype "bidirectional"))
    )
    (net (code "102") (name "TIM2CH4") (class "Default")
      (node (ref "U1") (pin "A5") (pinfunction "IO_L2N_0_A5") (pintype "bidirectional"))
      (node (ref "U3") (pin "17") (pinfunction "PA3-USART2RX/ADC3/TIM2CH4_17") (pintype "bidirectional"))
    )
    (net (code "103") (name "UART1_RX") (class "Default")
      (node (ref "U3") (pin "43") (pinfunction "PA10-USART1RX/TIM1CH3_43") (pintype "bidirectional"))
      (node (ref "X6") (pin "2") (pinfunction "2_2") (pintype "bidirectional"))
    )
    (net (code "104") (name "UART1_TX") (class "Default")
      (node (ref "U3") (pin "42") (pinfunction "PA9-USART1TX/TIM1CH2_42") (pintype "bidirectional"))
      (node (ref "X6") (pin "3") (pinfunction "3_3") (pintype "bidirectional"))
    )
    (net (code "105") (name "UART3_RX") (class "Default")
      (node (ref "U3") (pin "52") (pinfunction "PC11--USART3RX_52") (pintype "bidirectional"))
      (node (ref "X1") (pin "2") (pinfunction "2_2") (pintype "bidirectional"))
    )
    (net (code "106") (name "UART3_TX") (class "Default")
      (node (ref "U3") (pin "51") (pinfunction "PC10--USART3TX_51") (pintype "bidirectional"))
      (node (ref "X1") (pin "3") (pinfunction "3_3") (pintype "bidirectional"))
    )
    (net (code "107") (name "UART6_RX{slash}FTDI_ADBUS0") (class "Default")
      (node (ref "U1") (pin "H15") (pinfunction "IO_L37P_A7_M1A0_1_H15") (pintype "bidirectional"))
      (node (ref "U3") (pin "38") (pinfunction "PC7-TIM3CH2_38") (pintype "bidirectional"))
      (node (ref "U7") (pin "13") (pinfunction "AD0_13") (pintype "bidirectional"))
    )
    (net (code "108") (name "UART6_TX{slash}FTDI_ADBUS1") (class "Default")
      (node (ref "U1") (pin "G16") (pinfunction "IO_L36N_A8_M1BA1_1_G16") (pintype "bidirectional"))
      (node (ref "U3") (pin "37") (pinfunction "PC6-TIM3CH1_37") (pintype "bidirectional"))
      (node (ref "U7") (pin "14") (pinfunction "AD1_14") (pintype "bidirectional"))
    )
    (net (code "109") (name "USB_DM") (class "Default")
      (node (ref "J6") (pin "PIN_2") (pinfunction "2_PIN_2") (pintype "input"))
      (node (ref "U7") (pin "6") (pinfunction "DM_6") (pintype "bidirectional"))
    )
    (net (code "110") (name "USB_DP") (class "Default")
      (node (ref "J6") (pin "PIN_3") (pinfunction "3_PIN_3") (pintype "input"))
      (node (ref "U7") (pin "7") (pinfunction "DP_7") (pintype "bidirectional"))
    )
    (net (code "111") (name "V+") (class "Default")
      (node (ref "D1") (pin "2") (pinfunction "2_2") (pintype "bidirectional"))
      (node (ref "Q1") (pin "3") (pinfunction "D_3") (pintype "passive"))
      (node (ref "X1") (pin "5") (pinfunction "5_5") (pintype "bidirectional"))
      (node (ref "X3") (pin "12") (pinfunction "12_12") (pintype "bidirectional"))
      (node (ref "X6") (pin "5") (pinfunction "5_5") (pintype "bidirectional"))
    )
    (net (code "112") (name "VCC") (class "Default")
      (node (ref "C11") (pin "P$2") (pinfunction "2_P$2") (pintype "passive"))
      (node (ref "C37") (pin "P$1") (pinfunction "1_P$1") (pintype "passive"))
      (node (ref "C39") (pin "P$1") (pinfunction "1_P$1") (pintype "passive"))
      (node (ref "C40") (pin "P$1") (pinfunction "1_P$1") (pintype "passive"))
      (node (ref "C42") (pin "P$1") (pinfunction "1_P$1") (pintype "passive"))
      (node (ref "L2") (pin "P$2") (pinfunction "2_P$2") (pintype "passive"))
      (node (ref "R11") (pin "P$2") (pinfunction "2_P$2") (pintype "passive"))
      (node (ref "U10") (pin "11") (pinfunction "VCCVCO_11") (pintype "bidirectional"))
      (node (ref "U10") (pin "13") (pinfunction "VCCCP_13") (pintype "bidirectional"))
      (node (ref "U10") (pin "23") (pinfunction "VCCIF_23") (pintype "bidirectional"))
      (node (ref "U12") (pin "5") (pinfunction "VOUT_5") (pintype "bidirectional"))
    )
    (net (code "113") (name "VCCINT") (class "Default")
      (node (ref "C10") (pin "P$1") (pinfunction "1_P$1") (pintype "passive"))
      (node (ref "C17") (pin "P$1") (pinfunction "1_P$1") (pintype "passive"))
      (node (ref "C24") (pin "P$1") (pinfunction "1_P$1") (pintype "bidirectional"))
      (node (ref "C28") (pin "P$1") (pinfunction "1_P$1") (pintype "passive"))
      (node (ref "C29") (pin "P$1") (pinfunction "1_P$1") (pintype "passive"))
      (node (ref "C30") (pin "P$1") (pinfunction "1_P$1") (pintype "passive"))
      (node (ref "C31") (pin "P$1") (pinfunction "1_P$1") (pintype "passive"))
      (node (ref "C4") (pin "P$1") (pinfunction "1_P$1") (pintype "passive"))
      (node (ref "C43") (pin "P$1") (pinfunction "1_P$1") (pintype "passive"))
      (node (ref "C46") (pin "P$1") (pinfunction "1_P$1") (pintype "passive"))
      (node (ref "C5") (pin "P$1") (pinfunction "1_P$1") (pintype "passive"))
      (node (ref "C78") (pin "P$1") (pinfunction "1_P$1") (pintype "passive"))
      (node (ref "C80") (pin "P$1") (pinfunction "1_P$1") (pintype "passive"))
      (node (ref "C81") (pin "P$1") (pinfunction "1_P$1") (pintype "passive"))
      (node (ref "L14") (pin "2") (pinfunction "2_2") (pintype "bidirectional"))
      (node (ref "R64") (pin "P$2") (pinfunction "2_P$2") (pintype "passive"))
      (node (ref "U1") (pin "G7") (pinfunction "VCCINT_G7") (pintype "input"))
      (node (ref "U1") (pin "G9") (pinfunction "VCCINT_G9") (pintype "input"))
      (node (ref "U1") (pin "H10") (pinfunction "VCCINT_H10") (pintype "input"))
      (node (ref "U1") (pin "H8") (pinfunction "VCCINT_H8") (pintype "input"))
      (node (ref "U1") (pin "J7") (pinfunction "VCCINT_J7") (pintype "input"))
      (node (ref "U1") (pin "J9") (pinfunction "VCCINT_J9") (pintype "input"))
      (node (ref "U1") (pin "K10") (pinfunction "VCCINT_K10") (pintype "input"))
      (node (ref "U1") (pin "K8") (pinfunction "VCCINT_K8") (pintype "input"))
    )
    (net (code "114") (name "VCCIO") (class "Default")
      (node (ref "C1") (pin "P$2") (pinfunction "2_P$2") (pintype "passive"))
      (node (ref "C107") (pin "P$1") (pinfunction "1_P$1") (pintype "passive"))
      (node (ref "C21") (pin "P$1") (pinfunction "1_P$1") (pintype "bidirectional"))
      (node (ref "C22") (pin "P$1") (pinfunction "1_P$1") (pintype "passive"))
      (node (ref "C23") (pin "P$1") (pinfunction "1_P$1") (pintype "passive"))
      (node (ref "C25") (pin "P$1") (pinfunction "1_P$1") (pintype "bidirectional"))
      (node (ref "C26") (pin "P$1") (pinfunction "1_P$1") (pintype "bidirectional"))
      (node (ref "C27") (pin "P$1") (pinfunction "1_P$1") (pintype "passive"))
      (node (ref "C3") (pin "P$1") (pinfunction "1_P$1") (pintype "passive"))
      (node (ref "C33") (pin "P$2") (pinfunction "2_P$2") (pintype "passive"))
      (node (ref "C44") (pin "P$1") (pinfunction "1_P$1") (pintype "passive"))
      (node (ref "C45") (pin "1") (pinfunction "1_1") (pintype "passive"))
      (node (ref "C48") (pin "P$1") (pinfunction "1_P$1") (pintype "passive"))
      (node (ref "C50") (pin "P$2") (pinfunction "2_P$2") (pintype "passive"))
      (node (ref "C51") (pin "P$2") (pinfunction "2_P$2") (pintype "passive"))
      (node (ref "C52") (pin "P$1") (pinfunction "1_P$1") (pintype "passive"))
      (node (ref "C53") (pin "P$1") (pinfunction "1_P$1") (pintype "passive"))
      (node (ref "C54") (pin "P$1") (pinfunction "1_P$1") (pintype "passive"))
      (node (ref "C55") (pin "P$1") (pinfunction "1_P$1") (pintype "passive"))
      (node (ref "C56") (pin "P$1") (pinfunction "1_P$1") (pintype "passive"))
      (node (ref "C57") (pin "P$2") (pinfunction "2_P$2") (pintype "passive"))
      (node (ref "C58") (pin "P$1") (pinfunction "1_P$1") (pintype "passive"))
      (node (ref "C60") (pin "P$1") (pinfunction "1_P$1") (pintype "passive"))
      (node (ref "C61") (pin "P$1") (pinfunction "1_P$1") (pintype "passive"))
      (node (ref "C62") (pin "P$1") (pinfunction "1_P$1") (pintype "passive"))
      (node (ref "C63") (pin "P$1") (pinfunction "1_P$1") (pintype "passive"))
      (node (ref "C67") (pin "P$1") (pinfunction "1_P$1") (pintype "passive"))
      (node (ref "C69") (pin "1") (pinfunction "1_1") (pintype "passive"))
      (node (ref "C70") (pin "P$1") (pinfunction "1_P$1") (pintype "passive"))
      (node (ref "C71") (pin "P$1") (pinfunction "1_P$1") (pintype "passive"))
      (node (ref "C72") (pin "P$1") (pinfunction "1_P$1") (pintype "passive"))
      (node (ref "C73") (pin "P$1") (pinfunction "1_P$1") (pintype "passive"))
      (node (ref "C74") (pin "P$1") (pinfunction "1_P$1") (pintype "passive"))
      (node (ref "C76") (pin "P$1") (pinfunction "1_P$1") (pintype "passive"))
      (node (ref "C77") (pin "P$1") (pinfunction "1_P$1") (pintype "passive"))
      (node (ref "C8") (pin "P$1") (pinfunction "1_P$1") (pintype "passive"))
      (node (ref "C86") (pin "P$1") (pinfunction "1_P$1") (pintype "bidirectional"))
      (node (ref "C87") (pin "P$1") (pinfunction "1_P$1") (pintype "bidirectional"))
      (node (ref "C96") (pin "P$1") (pinfunction "1_P$1") (pintype "passive"))
      (node (ref "L10") (pin "P$1") (pinfunction "1_P$1") (pintype "passive"))
      (node (ref "L11") (pin "P$1") (pinfunction "1_P$1") (pintype "passive"))
      (node (ref "L13") (pin "1") (pinfunction "1_1") (pintype "bidirectional"))
      (node (ref "R12") (pin "P$2") (pinfunction "2_P$2") (pintype "passive"))
      (node (ref "R13") (pin "P$2") (pinfunction "2_P$2") (pintype "passive"))
      (node (ref "R15") (pin "P$1") (pinfunction "1_P$1") (pintype "passive"))
      (node (ref "R16") (pin "P$2") (pinfunction "2_P$2") (pintype "passive"))
      (node (ref "R17") (pin "P$1") (pinfunction "1_P$1") (pintype "passive"))
      (node (ref "R19") (pin "P$2") (pinfunction "2_P$2") (pintype "passive"))
      (node (ref "R28") (pin "P$1") (pinfunction "1_P$1") (pintype "passive"))
      (node (ref "R30") (pin "P$2") (pinfunction "2_P$2") (pintype "passive"))
      (node (ref "R34") (pin "P$2") (pinfunction "2_P$2") (pintype "passive"))
      (node (ref "R4") (pin "P$1") (pinfunction "1_P$1") (pintype "passive"))
      (node (ref "R5") (pin "P$1") (pinfunction "1_P$1") (pintype "passive"))
      (node (ref "R6") (pin "P$1") (pinfunction "1_P$1") (pintype "passive"))
      (node (ref "R61") (pin "P$2") (pinfunction "2_P$2") (pintype "passive"))
      (node (ref "U1") (pin "B13") (pinfunction "VCCO_0_B13") (pintype "input"))
      (node (ref "U1") (pin "B4") (pinfunction "VCCO_0_B4") (pintype "input"))
      (node (ref "U1") (pin "B9") (pinfunction "VCCO_0_B9") (pintype "input"))
      (node (ref "U1") (pin "D10") (pinfunction "VCCO_0_D10") (pintype "input"))
      (node (ref "U1") (pin "D15") (pinfunction "VCCO_1_D15") (pintype "input"))
      (node (ref "U1") (pin "D2") (pinfunction "VCCO_3_D2") (pintype "input"))
      (node (ref "U1") (pin "D7") (pinfunction "VCCO_0_D7") (pintype "input"))
      (node (ref "U1") (pin "E5") (pinfunction "VCCAUX_E5") (pintype "input"))
      (node (ref "U1") (pin "F11") (pinfunction "VCCAUX_F11") (pintype "input"))
      (node (ref "U1") (pin "F8") (pinfunction "VCCAUX_F8") (pintype "input"))
      (node (ref "U1") (pin "G10") (pinfunction "VCCAUX_G10") (pintype "input"))
      (node (ref "U1") (pin "G13") (pinfunction "VCCO_1_G13") (pintype "input"))
      (node (ref "U1") (pin "G4") (pinfunction "VCCO_3_G4") (pintype "input"))
      (node (ref "U1") (pin "H6") (pinfunction "VCCAUX_H6") (pintype "input"))
      (node (ref "U1") (pin "J10") (pinfunction "VCCAUX_J10") (pintype "input"))
      (node (ref "U1") (pin "J15") (pinfunction "VCCO_1_J15") (pintype "input"))
      (node (ref "U1") (pin "J2") (pinfunction "VCCO_3_J2") (pintype "input"))
      (node (ref "U1") (pin "K13") (pinfunction "VCCO_1_K13") (pintype "input"))
      (node (ref "U1") (pin "K4") (pinfunction "VCCO_3_K4") (pintype "input"))
      (node (ref "U1") (pin "L6") (pinfunction "VCCAUX_L6") (pintype "input"))
      (node (ref "U1") (pin "L9") (pinfunction "VCCAUX_L9") (pintype "input"))
      (node (ref "U1") (pin "N10") (pinfunction "VCCO_2_N10") (pintype "input"))
      (node (ref "U1") (pin "N15") (pinfunction "VCCO_1_N15") (pintype "input"))
      (node (ref "U1") (pin "N2") (pinfunction "VCCO_3_N2") (pintype "input"))
      (node (ref "U1") (pin "N7") (pinfunction "VCCO_2_N7") (pintype "input"))
      (node (ref "U1") (pin "R13") (pinfunction "VCCO_1_R13") (pintype "input"))
      (node (ref "U1") (pin "R4") (pinfunction "VCCO_2_R4") (pintype "input"))
      (node (ref "U1") (pin "R8") (pinfunction "VCCO_2_R8") (pintype "input"))
      (node (ref "U1") (pin "T11") (pinfunction "IO_L1N_M0_CMPMISO_2_T11") (pintype "bidirectional"))
      (node (ref "U10") (pin "14") (pinfunction "VCCD_14") (pintype "bidirectional"))
      (node (ref "U10") (pin "19") (pinfunction "VCCADC_19") (pintype "bidirectional"))
      (node (ref "U13") (pin "3") (pinfunction "NWP_3") (pintype "input"))
      (node (ref "U13") (pin "7") (pinfunction "NHOLD_7") (pintype "input"))
      (node (ref "U13") (pin "8") (pinfunction "VCC_8") (pintype "power_in"))
      (node (ref "U3") (pin "1") (pinfunction "VBAT_1") (pintype "power_in"))
      (node (ref "U3") (pin "13") (pinfunction "VDDA_13") (pintype "power_in"))
      (node (ref "U3") (pin "19") (pinfunction "VDD4_19") (pintype "bidirectional"))
      (node (ref "U3") (pin "32") (pinfunction "VDD1_32") (pintype "power_in"))
      (node (ref "U3") (pin "48") (pinfunction "VDD2_48") (pintype "power_in"))
      (node (ref "U3") (pin "64") (pinfunction "VDD3_64") (pintype "power_in"))
      (node (ref "U4") (pin "4") (pinfunction "VDD_4") (pintype "bidirectional"))
      (node (ref "U6") (pin "6") (pinfunction "VCC_6") (pintype "power_in"))
      (node (ref "U7") (pin "12") (pinfunction "VCCIO1_12") (pintype "power_in"))
      (node (ref "U7") (pin "24") (pinfunction "VCCIO2_24") (pintype "power_in"))
      (node (ref "U7") (pin "39") (pinfunction "VCCD_39") (pintype "bidirectional"))
      (node (ref "U7") (pin "40") (pinfunction "VREGIN_40") (pintype "power_in"))
      (node (ref "U7") (pin "46") (pinfunction "VCCIO3_46") (pintype "power_in"))
      (node (ref "X1") (pin "4") (pinfunction "4_4") (pintype "bidirectional"))
      (node (ref "X5") (pin "1") (pinfunction "1_1") (pintype "bidirectional"))
      (node (ref "X6") (pin "4") (pinfunction "4_4") (pintype "bidirectional"))
    )
    (net (code "115") (name "VDD") (class "Default")
      (node (ref "C2") (pin "P$1") (pinfunction "1_P$1") (pintype "passive"))
      (node (ref "C6") (pin "P$2") (pinfunction "2_P$2") (pintype "passive"))
      (node (ref "Q1") (pin "2") (pinfunction "S_2") (pintype "passive"))
      (node (ref "R1") (pin "P$2") (pinfunction "2_P$2") (pintype "passive"))
      (node (ref "R65") (pin "P$1") (pinfunction "1_P$1") (pintype "passive"))
      (node (ref "U2") (pin "2") (pinfunction "RUN/SS1_2") (pintype "bidirectional"))
      (node (ref "U2") (pin "3") (pinfunction "VIN_3") (pintype "bidirectional"))
      (node (ref "U2") (pin "6") (pinfunction "MODE/SYNC_6") (pintype "bidirectional"))
      (node (ref "U2") (pin "9") (pinfunction "RUN/SS2_9") (pintype "bidirectional"))
    )
    (net (code "116") (name "V_USB") (class "Default")
      (node (ref "D1") (pin "1") (pinfunction "1_1") (pintype "bidirectional"))
      (node (ref "J6") (pin "PIN_1") (pinfunction "1_PIN_1") (pintype "input"))
      (node (ref "R10") (pin "P$2") (pinfunction "2_P$2") (pintype "passive"))
      (node (ref "R8") (pin "P$2") (pinfunction "2_P$2") (pintype "passive"))
      (node (ref "R9") (pin "P$1") (pinfunction "1_P$1") (pintype "passive"))
    )
    (net (code "117") (name "unconnected-(J6-4-PadPIN_4)") (class "Default")
      (node (ref "J6") (pin "PIN_4") (pinfunction "4_PIN_4") (pintype "input"))
    )
    (net (code "118") (name "unconnected-(J6-S1-PadGND_LEFT)") (class "Default")
      (node (ref "J6") (pin "GND_LEFT") (pinfunction "S1_GND_LEFT") (pintype "passive"))
    )
    (net (code "119") (name "unconnected-(J6-S2-PadGND_RIGHT)") (class "Default")
      (node (ref "J6") (pin "GND_RIGHT") (pinfunction "S2_GND_RIGHT") (pintype "passive"))
    )
    (net (code "120") (name "unconnected-(J6-S3-PadGND_UP_LEFT)") (class "Default")
      (node (ref "J6") (pin "GND_UP_LEFT") (pinfunction "S3_GND_UP_LEFT") (pintype "passive"))
    )
    (net (code "121") (name "unconnected-(J6-S4-PadGND_UP_RIGHT)") (class "Default")
      (node (ref "J6") (pin "GND_UP_RIGHT") (pinfunction "S4_GND_UP_RIGHT") (pintype "passive"))
    )
    (net (code "122") (name "unconnected-(U1A-IO_L1N_VREF_0-PadA4)") (class "Default")
      (node (ref "U1") (pin "A4") (pinfunction "IO_L1N_VREF_0_A4") (pintype "bidirectional"))
    )
    (net (code "123") (name "unconnected-(U1A-IO_L2P_0-PadB5)") (class "Default")
      (node (ref "U1") (pin "B5") (pinfunction "IO_L2P_0_B5") (pintype "bidirectional"))
    )
    (net (code "124") (name "unconnected-(U1A-IO_L3N_0-PadC5)") (class "Default")
      (node (ref "U1") (pin "C5") (pinfunction "IO_L3N_0_C5") (pintype "bidirectional"))
    )
    (net (code "125") (name "unconnected-(U1A-IO_L3P_0-PadD5)") (class "Default")
      (node (ref "U1") (pin "D5") (pinfunction "IO_L3P_0_D5") (pintype "bidirectional"))
    )
    (net (code "126") (name "unconnected-(U1A-IO_L4N_0-PadA6)") (class "Default")
      (node (ref "U1") (pin "A6") (pinfunction "IO_L4N_0_A6") (pintype "bidirectional"))
    )
    (net (code "127") (name "unconnected-(U1A-IO_L4P_0-PadB6)") (class "Default")
      (node (ref "U1") (pin "B6") (pinfunction "IO_L4P_0_B6") (pintype "bidirectional"))
    )
    (net (code "128") (name "unconnected-(U1A-IO_L5N_0-PadE6)") (class "Default")
      (node (ref "U1") (pin "E6") (pinfunction "IO_L5N_0_E6") (pintype "bidirectional"))
    )
    (net (code "129") (name "unconnected-(U1A-IO_L5P_0-PadF7)") (class "Default")
      (node (ref "U1") (pin "F7") (pinfunction "IO_L5P_0_F7") (pintype "bidirectional"))
    )
    (net (code "130") (name "unconnected-(U1A-IO_L6P_0-PadC7)") (class "Default")
      (node (ref "U1") (pin "C7") (pinfunction "IO_L6P_0_C7") (pintype "bidirectional"))
    )
    (net (code "131") (name "unconnected-(U1A-IO_L7N_0-PadC6)") (class "Default")
      (node (ref "U1") (pin "C6") (pinfunction "IO_L7N_0_C6") (pintype "bidirectional"))
    )
    (net (code "132") (name "unconnected-(U1A-IO_L7P_0-PadD6)") (class "Default")
      (node (ref "U1") (pin "D6") (pinfunction "IO_L7P_0_D6") (pintype "bidirectional"))
    )
    (net (code "133") (name "unconnected-(U1A-IO_L33N_0-PadA8)") (class "Default")
      (node (ref "U1") (pin "A8") (pinfunction "IO_L33N_0_A8") (pintype "bidirectional"))
    )
    (net (code "134") (name "unconnected-(U1A-IO_L33P_0-PadB8)") (class "Default")
      (node (ref "U1") (pin "B8") (pinfunction "IO_L33P_0_B8") (pintype "bidirectional"))
    )
    (net (code "135") (name "unconnected-(U1A-IO_L34P_GCLK19_0-PadC9)") (class "Default")
      (node (ref "U1") (pin "C9") (pinfunction "IO_L34P_GCLK19_0_C9") (pintype "bidirectional"))
    )
    (net (code "136") (name "unconnected-(U1A-IO_L36N_GCLK14_0-PadE8)") (class "Default")
      (node (ref "U1") (pin "E8") (pinfunction "IO_L36N_GCLK14_0_E8") (pintype "bidirectional"))
    )
    (net (code "137") (name "unconnected-(U1A-IO_L36P_GCLK15_0-PadE7)") (class "Default")
      (node (ref "U1") (pin "E7") (pinfunction "IO_L36P_GCLK15_0_E7") (pintype "bidirectional"))
    )
    (net (code "138") (name "unconnected-(U1A-IO_L37P_GCLK13_0-PadE10)") (class "Default")
      (node (ref "U1") (pin "E10") (pinfunction "IO_L37P_GCLK13_0_E10") (pintype "bidirectional"))
    )
    (net (code "139") (name "unconnected-(U1A-IO_L38N_VREF_0-PadC8)") (class "Default")
      (node (ref "U1") (pin "C8") (pinfunction "IO_L38N_VREF_0_C8") (pintype "bidirectional"))
    )
    (net (code "140") (name "unconnected-(U1A-IO_L38P_0-PadD8)") (class "Default")
      (node (ref "U1") (pin "D8") (pinfunction "IO_L38P_0_D8") (pintype "bidirectional"))
    )
    (net (code "141") (name "unconnected-(U1A-IO_L39N_0-PadA11)") (class "Default")
      (node (ref "U1") (pin "A11") (pinfunction "IO_L39N_0_A11") (pintype "bidirectional"))
    )
    (net (code "142") (name "unconnected-(U1A-IO_L40N_0-PadD9)") (class "Default")
      (node (ref "U1") (pin "D9") (pinfunction "IO_L40N_0_D9") (pintype "bidirectional"))
    )
    (net (code "143") (name "unconnected-(U1A-IO_L40P_0-PadF9)") (class "Default")
      (node (ref "U1") (pin "F9") (pinfunction "IO_L40P_0_F9") (pintype "bidirectional"))
    )
    (net (code "144") (name "unconnected-(U1A-IO_L62P_0-PadB12)") (class "Default")
      (node (ref "U1") (pin "B12") (pinfunction "IO_L62P_0_B12") (pintype "bidirectional"))
    )
    (net (code "145") (name "unconnected-(U1A-IO_L63N_SCP6_0-PadA13)") (class "Default")
      (node (ref "U1") (pin "A13") (pinfunction "IO_L63N_SCP6_0_A13") (pintype "bidirectional"))
    )
    (net (code "146") (name "unconnected-(U1A-IO_L63P_SCP7_0-PadC13)") (class "Default")
      (node (ref "U1") (pin "C13") (pinfunction "IO_L63P_SCP7_0_C13") (pintype "bidirectional"))
    )
    (net (code "147") (name "unconnected-(U1A-IO_L64N_SCP4_0-PadE11)") (class "Default")
      (node (ref "U1") (pin "E11") (pinfunction "IO_L64N_SCP4_0_E11") (pintype "bidirectional"))
    )
    (net (code "148") (name "unconnected-(U1A-IO_L64P_SCP5_0-PadF10)") (class "Default")
      (node (ref "U1") (pin "F10") (pinfunction "IO_L64P_SCP5_0_F10") (pintype "bidirectional"))
    )
    (net (code "149") (name "unconnected-(U1A-IO_L65N_SCP2_0-PadA14)") (class "Default")
      (node (ref "U1") (pin "A14") (pinfunction "IO_L65N_SCP2_0_A14") (pintype "bidirectional"))
    )
    (net (code "150") (name "unconnected-(U1A-IO_L65P_SCP3_0-PadB14)") (class "Default")
      (node (ref "U1") (pin "B14") (pinfunction "IO_L65P_SCP3_0_B14") (pintype "bidirectional"))
    )
    (net (code "151") (name "unconnected-(U1A-IO_L66N_SCP0_0-PadD12)") (class "Default")
      (node (ref "U1") (pin "D12") (pinfunction "IO_L66N_SCP0_0_D12") (pintype "bidirectional"))
    )
    (net (code "152") (name "unconnected-(U1A-IO_L66P_SCP1_0-PadD11)") (class "Default")
      (node (ref "U1") (pin "D11") (pinfunction "IO_L66P_SCP1_0_D11") (pintype "bidirectional"))
    )
    (net (code "153") (name "unconnected-(U1B-IO_L1N_A24_VREF_1-PadE12)") (class "Default")
      (node (ref "U1") (pin "E12") (pinfunction "IO_L1N_A24_VREF_1_E12") (pintype "bidirectional"))
    )
    (net (code "154") (name "unconnected-(U1B-IO_L1P_A25_1-PadE13)") (class "Default")
      (node (ref "U1") (pin "E13") (pinfunction "IO_L1P_A25_1_E13") (pintype "bidirectional"))
    )
    (net (code "155") (name "unconnected-(U1B-IO_L29N_A22_M1A14_1-PadB16)") (class "Default")
      (node (ref "U1") (pin "B16") (pinfunction "IO_L29N_A22_M1A14_1_B16") (pintype "bidirectional"))
    )
    (net (code "156") (name "unconnected-(U1B-IO_L29P_A23_M1A13_1-PadB15)") (class "Default")
      (node (ref "U1") (pin "B15") (pinfunction "IO_L29P_A23_M1A13_1_B15") (pintype "bidirectional"))
    )
    (net (code "157") (name "unconnected-(U1B-IO_L30N_A20_M1A11_1-PadG11)") (class "Default")
      (node (ref "U1") (pin "G11") (pinfunction "IO_L30N_A20_M1A11_1_G11") (pintype "bidirectional"))
    )
    (net (code "158") (name "unconnected-(U1B-IO_L30P_A21_M1RESET_1-PadF12)") (class "Default")
      (node (ref "U1") (pin "F12") (pinfunction "IO_L30P_A21_M1RESET_1_F12") (pintype "bidirectional"))
    )
    (net (code "159") (name "unconnected-(U1B-IO_L31N_A18_M1A12_1-PadD16)") (class "Default")
      (node (ref "U1") (pin "D16") (pinfunction "IO_L31N_A18_M1A12_1_D16") (pintype "bidirectional"))
    )
    (net (code "160") (name "unconnected-(U1B-IO_L31P_A19_M1CKE_1-PadD14)") (class "Default")
      (node (ref "U1") (pin "D14") (pinfunction "IO_L31P_A19_M1CKE_1_D14") (pintype "bidirectional"))
    )
    (net (code "161") (name "unconnected-(U1B-IO_L32N_A16_M1A9_1-PadF14)") (class "Default")
      (node (ref "U1") (pin "F14") (pinfunction "IO_L32N_A16_M1A9_1_F14") (pintype "bidirectional"))
    )
    (net (code "162") (name "unconnected-(U1B-IO_L32P_A17_M1A8_1-PadF13)") (class "Default")
      (node (ref "U1") (pin "F13") (pinfunction "IO_L32P_A17_M1A8_1_F13") (pintype "bidirectional"))
    )
    (net (code "163") (name "unconnected-(U1B-IO_L33N_A14_M1A4_1-PadC16)") (class "Default")
      (node (ref "U1") (pin "C16") (pinfunction "IO_L33N_A14_M1A4_1_C16") (pintype "bidirectional"))
    )
    (net (code "164") (name "unconnected-(U1B-IO_L33P_A15_M1A10_1-PadC15)") (class "Default")
      (node (ref "U1") (pin "C15") (pinfunction "IO_L33P_A15_M1A10_1_C15") (pintype "bidirectional"))
    )
    (net (code "165") (name "unconnected-(U1B-IO_L36P_A9_M1BA0_1-PadG14)") (class "Default")
      (node (ref "U1") (pin "G14") (pinfunction "IO_L36P_A9_M1BA0_1_G14") (pintype "bidirectional"))
    )
    (net (code "166") (name "unconnected-(U1B-IO_L37N_A6_M1A1_1-PadH16)") (class "Default")
      (node (ref "U1") (pin "H16") (pinfunction "IO_L37N_A6_M1A1_1_H16") (pintype "bidirectional"))
    )
    (net (code "167") (name "unconnected-(U1B-IO_L38N_A4_M1CLKN_1-PadH11)") (class "Default")
      (node (ref "U1") (pin "H11") (pinfunction "IO_L38N_A4_M1CLKN_1_H11") (pintype "bidirectional"))
    )
    (net (code "168") (name "unconnected-(U1B-IO_L38P_A5_M1CLK_1-PadG12)") (class "Default")
      (node (ref "U1") (pin "G12") (pinfunction "IO_L38P_A5_M1CLK_1_G12") (pintype "bidirectional"))
    )
    (net (code "169") (name "unconnected-(U1B-IO_L39N_M1ODT_1-PadH14)") (class "Default")
      (node (ref "U1") (pin "H14") (pinfunction "IO_L39N_M1ODT_1_H14") (pintype "bidirectional"))
    )
    (net (code "170") (name "unconnected-(U1B-IO_L39P_M1A3_1-PadH13)") (class "Default")
      (node (ref "U1") (pin "H13") (pinfunction "IO_L39P_M1A3_1_H13") (pintype "bidirectional"))
    )
    (net (code "171") (name "unconnected-(U1B-IO_L40N_GCLK10_M1A6_1-PadJ12)") (class "Default")
      (node (ref "U1") (pin "J12") (pinfunction "IO_L40N_GCLK10_M1A6_1_J12") (pintype "bidirectional"))
    )
    (net (code "172") (name "unconnected-(U1B-IO_L40P_GCLK11_M1A5_1-PadJ11)") (class "Default")
      (node (ref "U1") (pin "J11") (pinfunction "IO_L40P_GCLK11_M1A5_1_J11") (pintype "bidirectional"))
    )
    (net (code "173") (name "unconnected-(U1B-IO_L41P_GCLK9_IRDY1_M1RASN_1-PadJ13)") (class "Default")
      (node (ref "U1") (pin "J13") (pinfunction "IO_L41P_GCLK9_IRDY1_M1RASN_1_J13") (pintype "bidirectional"))
    )
    (net (code "174") (name "unconnected-(U1B-IO_L42N_GCLK6_TRDY1_M1LDM_1-PadK11)") (class "Default")
      (node (ref "U1") (pin "K11") (pinfunction "IO_L42N_GCLK6_TRDY1_M1LDM_1_K11") (pintype "bidirectional"))
    )
    (net (code "175") (name "unconnected-(U1B-IO_L42P_GCLK7_M1UDM_1-PadK12)") (class "Default")
      (node (ref "U1") (pin "K12") (pinfunction "IO_L42P_GCLK7_M1UDM_1_K12") (pintype "bidirectional"))
    )
    (net (code "176") (name "unconnected-(U1B-IO_L43N_GCLK4_M1DQ5_1-PadJ16)") (class "Default")
      (node (ref "U1") (pin "J16") (pinfunction "IO_L43N_GCLK4_M1DQ5_1_J16") (pintype "bidirectional"))
    )
    (net (code "177") (name "unconnected-(U1B-IO_L48P_HDC_M1DQ8_1-PadP15)") (class "Default")
      (node (ref "U1") (pin "P15") (pinfunction "IO_L48P_HDC_M1DQ8_1_P15") (pintype "bidirectional"))
    )
    (net (code "178") (name "unconnected-(U1B-IO_L49N_M1DQ11_1-PadR16)") (class "Default")
      (node (ref "U1") (pin "R16") (pinfunction "IO_L49N_M1DQ11_1_R16") (pintype "bidirectional"))
    )
    (net (code "179") (name "unconnected-(U1B-IO_L50P_M1UDQS_1-PadR14)") (class "Default")
      (node (ref "U1") (pin "R14") (pinfunction "IO_L50P_M1UDQS_1_R14") (pintype "bidirectional"))
    )
    (net (code "180") (name "unconnected-(U1B-IO_L51N_M1DQ13_1-PadT13)") (class "Default")
      (node (ref "U1") (pin "T13") (pinfunction "IO_L51N_M1DQ13_1_T13") (pintype "bidirectional"))
    )
    (net (code "181") (name "unconnected-(U1B-IO_L51P_M1DQ12_1-PadT14)") (class "Default")
      (node (ref "U1") (pin "T14") (pinfunction "IO_L51P_M1DQ12_1_T14") (pintype "bidirectional"))
    )
    (net (code "182") (name "unconnected-(U1B-IO_L52N_M1DQ15_1-PadT12)") (class "Default")
      (node (ref "U1") (pin "T12") (pinfunction "IO_L52N_M1DQ15_1_T12") (pintype "bidirectional"))
    )
    (net (code "183") (name "unconnected-(U1B-IO_L52P_M1DQ14_1-PadR12)") (class "Default")
      (node (ref "U1") (pin "R12") (pinfunction "IO_L52P_M1DQ14_1_R12") (pintype "bidirectional"))
    )
    (net (code "184") (name "unconnected-(U1B-IO_L53N_VREF_1-PadL13)") (class "Default")
      (node (ref "U1") (pin "L13") (pinfunction "IO_L53N_VREF_1_L13") (pintype "bidirectional"))
    )
    (net (code "185") (name "unconnected-(U1B-IO_L53P_1-PadL12)") (class "Default")
      (node (ref "U1") (pin "L12") (pinfunction "IO_L53P_1_L12") (pintype "bidirectional"))
    )
    (net (code "186") (name "unconnected-(U1B-IO_L74P_AWAKE_1-PadM13)") (class "Default")
      (node (ref "U1") (pin "M13") (pinfunction "IO_L74P_AWAKE_1_M13") (pintype "bidirectional"))
    )
    (net (code "187") (name "unconnected-(U1C-CMPCS_B_2-PadL11)") (class "Default")
      (node (ref "U1") (pin "L11") (pinfunction "CMPCS_B_2_L11") (pintype "bidirectional"))
    )
    (net (code "188") (name "unconnected-(U1C-IO_L2N_CMPMOSI_2-PadM11)") (class "Default")
      (node (ref "U1") (pin "M11") (pinfunction "IO_L2N_CMPMOSI_2_M11") (pintype "bidirectional"))
    )
    (net (code "189") (name "unconnected-(U1C-IO_L2P_CMPCLK_2-PadM12)") (class "Default")
      (node (ref "U1") (pin "M12") (pinfunction "IO_L2P_CMPCLK_2_M12") (pintype "bidirectional"))
    )
    (net (code "190") (name "unconnected-(U1C-IO_L12N_D2_MISO3_2-PadP12)") (class "Default")
      (node (ref "U1") (pin "P12") (pinfunction "IO_L12N_D2_MISO3_2_P12") (pintype "bidirectional"))
    )
    (net (code "191") (name "unconnected-(U1C-IO_L12P_D1_MISO2_2-PadN12)") (class "Default")
      (node (ref "U1") (pin "N12") (pinfunction "IO_L12P_D1_MISO2_2_N12") (pintype "bidirectional"))
    )
    (net (code "192") (name "unconnected-(U1C-IO_L13N_D10_2-PadP11)") (class "Default")
      (node (ref "U1") (pin "P11") (pinfunction "IO_L13N_D10_2_P11") (pintype "bidirectional"))
    )
    (net (code "193") (name "unconnected-(U1C-IO_L14P_D11_2-PadN9)") (class "Default")
      (node (ref "U1") (pin "N9") (pinfunction "IO_L14P_D11_2_N9") (pintype "bidirectional"))
    )
    (net (code "194") (name "unconnected-(U1C-IO_L16N_VREF_2-PadM10)") (class "Default")
      (node (ref "U1") (pin "M10") (pinfunction "IO_L16N_VREF_2_M10") (pintype "bidirectional"))
    )
    (net (code "195") (name "unconnected-(U1C-IO_L16P_2-PadL10)") (class "Default")
      (node (ref "U1") (pin "L10") (pinfunction "IO_L16P_2_L10") (pintype "bidirectional"))
    )
    (net (code "196") (name "unconnected-(U1C-IO_L23N_2-PadT9)") (class "Default")
      (node (ref "U1") (pin "T9") (pinfunction "IO_L23N_2_T9") (pintype "bidirectional"))
    )
    (net (code "197") (name "unconnected-(U1C-IO_L23P_2-PadR9)") (class "Default")
      (node (ref "U1") (pin "R9") (pinfunction "IO_L23P_2_R9") (pintype "bidirectional"))
    )
    (net (code "198") (name "unconnected-(U1C-IO_L29N_GCLK2_2-PadN8)") (class "Default")
      (node (ref "U1") (pin "N8") (pinfunction "IO_L29N_GCLK2_2_N8") (pintype "bidirectional"))
    )
    (net (code "199") (name "unconnected-(U1C-IO_L29P_GCLK3_2-PadM9)") (class "Default")
      (node (ref "U1") (pin "M9") (pinfunction "IO_L29P_GCLK3_2_M9") (pintype "bidirectional"))
    )
    (net (code "200") (name "unconnected-(U1C-IO_L30N_GCLK0_USERCCLK_2-PadT8)") (class "Default")
      (node (ref "U1") (pin "T8") (pinfunction "IO_L30N_GCLK0_USERCCLK_2_T8") (pintype "bidirectional"))
    )
    (net (code "201") (name "unconnected-(U1C-IO_L30P_GCLK1_D13_2-PadP8)") (class "Default")
      (node (ref "U1") (pin "P8") (pinfunction "IO_L30P_GCLK1_D13_2_P8") (pintype "bidirectional"))
    )
    (net (code "202") (name "unconnected-(U1C-IO_L31N_GCLK30_D15_2-PadM7)") (class "Default")
      (node (ref "U1") (pin "M7") (pinfunction "IO_L31N_GCLK30_D15_2_M7") (pintype "bidirectional"))
    )
    (net (code "203") (name "unconnected-(U1C-IO_L31P_GCLK31_D14_2-PadP7)") (class "Default")
      (node (ref "U1") (pin "P7") (pinfunction "IO_L31P_GCLK31_D14_2_P7") (pintype "bidirectional"))
    )
    (net (code "204") (name "unconnected-(U1C-IO_L32N_GCLK28_2-PadT7)") (class "Default")
      (node (ref "U1") (pin "T7") (pinfunction "IO_L32N_GCLK28_2_T7") (pintype "bidirectional"))
    )
    (net (code "205") (name "unconnected-(U1C-IO_L32P_GCLK29_2-PadR7)") (class "Default")
      (node (ref "U1") (pin "R7") (pinfunction "IO_L32P_GCLK29_2_R7") (pintype "bidirectional"))
    )
    (net (code "206") (name "unconnected-(U1C-IO_L47N_2-PadT6)") (class "Default")
      (node (ref "U1") (pin "T6") (pinfunction "IO_L47N_2_T6") (pintype "bidirectional"))
    )
    (net (code "207") (name "unconnected-(U1C-IO_L47P_2-PadP6)") (class "Default")
      (node (ref "U1") (pin "P6") (pinfunction "IO_L47P_2_P6") (pintype "bidirectional"))
    )
    (net (code "208") (name "unconnected-(U1C-IO_L48N_RDWR_B_VREF_2-PadT5)") (class "Default")
      (node (ref "U1") (pin "T5") (pinfunction "IO_L48N_RDWR_B_VREF_2_T5") (pintype "bidirectional"))
    )
    (net (code "209") (name "unconnected-(U1C-IO_L48P_D7_2-PadR5)") (class "Default")
      (node (ref "U1") (pin "R5") (pinfunction "IO_L48P_D7_2_R5") (pintype "bidirectional"))
    )
    (net (code "210") (name "unconnected-(U1C-IO_L49N_D4_2-PadP5)") (class "Default")
      (node (ref "U1") (pin "P5") (pinfunction "IO_L49N_D4_2_P5") (pintype "bidirectional"))
    )
    (net (code "211") (name "unconnected-(U1C-IO_L49P_D3_2-PadN5)") (class "Default")
      (node (ref "U1") (pin "N5") (pinfunction "IO_L49P_D3_2_N5") (pintype "bidirectional"))
    )
    (net (code "212") (name "unconnected-(U1C-IO_L62N_D6_2-PadL7)") (class "Default")
      (node (ref "U1") (pin "L7") (pinfunction "IO_L62N_D6_2_L7") (pintype "bidirectional"))
    )
    (net (code "213") (name "unconnected-(U1C-IO_L62P_D5_2-PadL8)") (class "Default")
      (node (ref "U1") (pin "L8") (pinfunction "IO_L62P_D5_2_L8") (pintype "bidirectional"))
    )
    (net (code "214") (name "unconnected-(U1C-IO_L63N_2-PadT4)") (class "Default")
      (node (ref "U1") (pin "T4") (pinfunction "IO_L63N_2_T4") (pintype "bidirectional"))
    )
    (net (code "215") (name "unconnected-(U1C-IO_L63P_2-PadP4)") (class "Default")
      (node (ref "U1") (pin "P4") (pinfunction "IO_L63P_2_P4") (pintype "bidirectional"))
    )
    (net (code "216") (name "unconnected-(U1C-IO_L64N_D9_2-PadN6)") (class "Default")
      (node (ref "U1") (pin "N6") (pinfunction "IO_L64N_D9_2_N6") (pintype "bidirectional"))
    )
    (net (code "217") (name "unconnected-(U1C-IO_L64P_D8_2-PadM6)") (class "Default")
      (node (ref "U1") (pin "M6") (pinfunction "IO_L64P_D8_2_M6") (pintype "bidirectional"))
    )
    (net (code "218") (name "unconnected-(U1D-IO_L1N_VREF_3-PadM3)") (class "Default")
      (node (ref "U1") (pin "M3") (pinfunction "IO_L1N_VREF_3_M3") (pintype "bidirectional"))
    )
    (net (code "219") (name "unconnected-(U1D-IO_L1P_3-PadM4)") (class "Default")
      (node (ref "U1") (pin "M4") (pinfunction "IO_L1P_3_M4") (pintype "bidirectional"))
    )
    (net (code "220") (name "unconnected-(U1D-IO_L2N_3-PadN4)") (class "Default")
      (node (ref "U1") (pin "N4") (pinfunction "IO_L2N_3_N4") (pintype "bidirectional"))
    )
    (net (code "221") (name "unconnected-(U1D-IO_L2P_3-PadM5)") (class "Default")
      (node (ref "U1") (pin "M5") (pinfunction "IO_L2P_3_M5") (pintype "bidirectional"))
    )
    (net (code "222") (name "unconnected-(U1D-IO_L32P_M3DQ14_3-PadR2)") (class "Default")
      (node (ref "U1") (pin "R2") (pinfunction "IO_L32P_M3DQ14_3_R2") (pintype "bidirectional"))
    )
    (net (code "223") (name "unconnected-(U1D-IO_L33N_M3DQ13_3-PadP1)") (class "Default")
      (node (ref "U1") (pin "P1") (pinfunction "IO_L33N_M3DQ13_3_P1") (pintype "bidirectional"))
    )
    (net (code "224") (name "unconnected-(U1D-IO_L33P_M3DQ12_3-PadP2)") (class "Default")
      (node (ref "U1") (pin "P2") (pinfunction "IO_L33P_M3DQ12_3_P2") (pintype "bidirectional"))
    )
    (net (code "225") (name "unconnected-(U1D-IO_L34P_M3UDQS_3-PadN3)") (class "Default")
      (node (ref "U1") (pin "N3") (pinfunction "IO_L34P_M3UDQS_3_N3") (pintype "bidirectional"))
    )
    (net (code "226") (name "unconnected-(U1D-IO_L35P_M3DQ10_3-PadM2)") (class "Default")
      (node (ref "U1") (pin "M2") (pinfunction "IO_L35P_M3DQ10_3_M2") (pintype "bidirectional"))
    )
    (net (code "227") (name "unconnected-(U1D-IO_L36P_M3DQ8_3-PadL3)") (class "Default")
      (node (ref "U1") (pin "L3") (pinfunction "IO_L36P_M3DQ8_3_L3") (pintype "bidirectional"))
    )
    (net (code "228") (name "unconnected-(U1D-IO_L37N_M3DQ1_3-PadK1)") (class "Default")
      (node (ref "U1") (pin "K1") (pinfunction "IO_L37N_M3DQ1_3_K1") (pintype "bidirectional"))
    )
    (net (code "229") (name "unconnected-(U1D-IO_L37P_M3DQ0_3-PadK2)") (class "Default")
      (node (ref "U1") (pin "K2") (pinfunction "IO_L37P_M3DQ0_3_K2") (pintype "bidirectional"))
    )
    (net (code "230") (name "unconnected-(U1D-IO_L38P_M3DQ2_3-PadJ3)") (class "Default")
      (node (ref "U1") (pin "J3") (pinfunction "IO_L38P_M3DQ2_3_J3") (pintype "bidirectional"))
    )
    (net (code "231") (name "unconnected-(U1D-IO_L39N_M3LDQSN_3-PadH1)") (class "Default")
      (node (ref "U1") (pin "H1") (pinfunction "IO_L39N_M3LDQSN_3_H1") (pintype "bidirectional"))
    )
    (net (code "232") (name "unconnected-(U1D-IO_L39P_M3LDQS_3-PadH2)") (class "Default")
      (node (ref "U1") (pin "H2") (pinfunction "IO_L39P_M3LDQS_3_H2") (pintype "bidirectional"))
    )
    (net (code "233") (name "unconnected-(U1D-IO_L40N_M3DQ7_3-PadG1)") (class "Default")
      (node (ref "U1") (pin "G1") (pinfunction "IO_L40N_M3DQ7_3_G1") (pintype "bidirectional"))
    )
    (net (code "234") (name "unconnected-(U1D-IO_L40P_M3DQ6_3-PadG3)") (class "Default")
      (node (ref "U1") (pin "G3") (pinfunction "IO_L40P_M3DQ6_3_G3") (pintype "bidirectional"))
    )
    (net (code "235") (name "unconnected-(U1D-IO_L41P_GCLK27_M3DQ4_3-PadF2)") (class "Default")
      (node (ref "U1") (pin "F2") (pinfunction "IO_L41P_GCLK27_M3DQ4_3_F2") (pintype "bidirectional"))
    )
    (net (code "236") (name "unconnected-(U1D-IO_L42N_GCLK24_M3LDM_3-PadJ4)") (class "Default")
      (node (ref "U1") (pin "J4") (pinfunction "IO_L42N_GCLK24_M3LDM_3_J4") (pintype "bidirectional"))
    )
    (net (code "237") (name "unconnected-(U1D-IO_L42P_GCLK25_TRDY2_M3UDM_3-PadK3)") (class "Default")
      (node (ref "U1") (pin "K3") (pinfunction "IO_L42P_GCLK25_TRDY2_M3UDM_3_K3") (pintype "bidirectional"))
    )
    (net (code "238") (name "unconnected-(U1D-IO_L43N_GCLK22_IRDY2_M3CASN_3-PadH5)") (class "Default")
      (node (ref "U1") (pin "H5") (pinfunction "IO_L43N_GCLK22_IRDY2_M3CASN_3_H5") (pintype "bidirectional"))
    )
    (net (code "239") (name "unconnected-(U1D-IO_L43P_GCLK23_M3RASN_3-PadJ6)") (class "Default")
      (node (ref "U1") (pin "J6") (pinfunction "IO_L43P_GCLK23_M3RASN_3_J6") (pintype "bidirectional"))
    )
    (net (code "240") (name "unconnected-(U1D-IO_L44P_GCLK21_M3A5_3-PadH4)") (class "Default")
      (node (ref "U1") (pin "H4") (pinfunction "IO_L44P_GCLK21_M3A5_3_H4") (pintype "bidirectional"))
    )
    (net (code "241") (name "unconnected-(U1D-IO_L45N_M3ODT_3-PadL5)") (class "Default")
      (node (ref "U1") (pin "L5") (pinfunction "IO_L45N_M3ODT_3_L5") (pintype "bidirectional"))
    )
    (net (code "242") (name "unconnected-(U1D-IO_L45P_M3A3_3-PadL4)") (class "Default")
      (node (ref "U1") (pin "L4") (pinfunction "IO_L45P_M3A3_3_L4") (pintype "bidirectional"))
    )
    (net (code "243") (name "unconnected-(U1D-IO_L46P_M3CLK_3-PadE2)") (class "Default")
      (node (ref "U1") (pin "E2") (pinfunction "IO_L46P_M3CLK_3_E2") (pintype "bidirectional"))
    )
    (net (code "244") (name "unconnected-(U1D-IO_L47N_M3A1_3-PadK6)") (class "Default")
      (node (ref "U1") (pin "K6") (pinfunction "IO_L47N_M3A1_3_K6") (pintype "bidirectional"))
    )
    (net (code "245") (name "unconnected-(U1D-IO_L47P_M3A0_3-PadK5)") (class "Default")
      (node (ref "U1") (pin "K5") (pinfunction "IO_L47P_M3A0_3_K5") (pintype "bidirectional"))
    )
    (net (code "246") (name "unconnected-(U1D-IO_L48N_M3BA1_3-PadC2)") (class "Default")
      (node (ref "U1") (pin "C2") (pinfunction "IO_L48N_M3BA1_3_C2") (pintype "bidirectional"))
    )
    (net (code "247") (name "unconnected-(U1D-IO_L48P_M3BA0_3-PadC3)") (class "Default")
      (node (ref "U1") (pin "C3") (pinfunction "IO_L48P_M3BA0_3_C3") (pintype "bidirectional"))
    )
    (net (code "248") (name "unconnected-(U1D-IO_L49P_M3A7_3-PadD3)") (class "Default")
      (node (ref "U1") (pin "D3") (pinfunction "IO_L49P_M3A7_3_D3") (pintype "bidirectional"))
    )
    (net (code "249") (name "unconnected-(U1D-IO_L50N_M3BA2_3-PadB1)") (class "Default")
      (node (ref "U1") (pin "B1") (pinfunction "IO_L50N_M3BA2_3_B1") (pintype "bidirectional"))
    )
    (net (code "250") (name "unconnected-(U1D-IO_L51N_M3A4_3-PadG5)") (class "Default")
      (node (ref "U1") (pin "G5") (pinfunction "IO_L51N_M3A4_3_G5") (pintype "bidirectional"))
    )
    (net (code "251") (name "unconnected-(U1D-IO_L51P_M3A10_3-PadG6)") (class "Default")
      (node (ref "U1") (pin "G6") (pinfunction "IO_L51P_M3A10_3_G6") (pintype "bidirectional"))
    )
    (net (code "252") (name "unconnected-(U1D-IO_L52N_M3A9_3-PadA2)") (class "Default")
      (node (ref "U1") (pin "A2") (pinfunction "IO_L52N_M3A9_3_A2") (pintype "bidirectional"))
    )
    (net (code "253") (name "unconnected-(U1D-IO_L52P_M3A8_3-PadB2)") (class "Default")
      (node (ref "U1") (pin "B2") (pinfunction "IO_L52P_M3A8_3_B2") (pintype "bidirectional"))
    )
    (net (code "254") (name "unconnected-(U1D-IO_L53N_M3A12_3-PadF3)") (class "Default")
      (node (ref "U1") (pin "F3") (pinfunction "IO_L53N_M3A12_3_F3") (pintype "bidirectional"))
    )
    (net (code "255") (name "unconnected-(U1D-IO_L53P_M3CKE_3-PadF4)") (class "Default")
      (node (ref "U1") (pin "F4") (pinfunction "IO_L53P_M3CKE_3_F4") (pintype "bidirectional"))
    )
    (net (code "256") (name "unconnected-(U1D-IO_L54N_M3A11_3-PadE3)") (class "Default")
      (node (ref "U1") (pin "E3") (pinfunction "IO_L54N_M3A11_3_E3") (pintype "bidirectional"))
    )
    (net (code "257") (name "unconnected-(U1D-IO_L54P_M3RESET_3-PadE4)") (class "Default")
      (node (ref "U1") (pin "E4") (pinfunction "IO_L54P_M3RESET_3_E4") (pintype "bidirectional"))
    )
    (net (code "258") (name "unconnected-(U1D-IO_L55N_M3A14_3-PadF5)") (class "Default")
      (node (ref "U1") (pin "F5") (pinfunction "IO_L55N_M3A14_3_F5") (pintype "bidirectional"))
    )
    (net (code "259") (name "unconnected-(U1D-IO_L55P_M3A13_3-PadF6)") (class "Default")
      (node (ref "U1") (pin "F6") (pinfunction "IO_L55P_M3A13_3_F6") (pintype "bidirectional"))
    )
    (net (code "260") (name "unconnected-(U1D-IO_L83N_VREF_3-PadA3)") (class "Default")
      (node (ref "U1") (pin "A3") (pinfunction "IO_L83N_VREF_3_A3") (pintype "bidirectional"))
    )
    (net (code "261") (name "unconnected-(U1D-IO_L83P_3-PadB3)") (class "Default")
      (node (ref "U1") (pin "B3") (pinfunction "IO_L83P_3_B3") (pintype "bidirectional"))
    )
    (net (code "262") (name "unconnected-(U3-PA11-USART1CTS{slash}CANRX{slash}USBDM{slash}TIM1CH4-Pad44)") (class "Default")
      (node (ref "U3") (pin "44") (pinfunction "PA11-USART1CTS/CANRX/USBDM/TIM1CH4_44") (pintype "bidirectional"))
    )
    (net (code "263") (name "unconnected-(U3-PA12-USART1RTS{slash}CANTX{slash}USBDP{slash}TIM1ETR-Pad45)") (class "Default")
      (node (ref "U3") (pin "45") (pinfunction "PA12-USART1RTS/CANTX/USBDP/TIM1ETR_45") (pintype "bidirectional"))
    )
    (net (code "264") (name "unconnected-(U3-PB2{slash}BOOT1-Pad28)") (class "Default")
      (node (ref "U3") (pin "28") (pinfunction "PB2/BOOT1_28") (pintype "bidirectional"))
    )
    (net (code "265") (name "unconnected-(U3-PB4{slash}JNTRST--TIM3CH1{slash}SPI1MISO-Pad56)") (class "Default")
      (node (ref "U3") (pin "56") (pinfunction "PB4/JNTRST--TIM3CH1/SPI1MISO_56") (pintype "bidirectional"))
    )
    (net (code "266") (name "unconnected-(U3-PB5-I2C1SMBAI-TIM3CH2{slash}SPI1MOSI-Pad57)") (class "Default")
      (node (ref "U3") (pin "57") (pinfunction "PB5-I2C1SMBAI-TIM3CH2/SPI1MOSI_57") (pintype "bidirectional"))
    )
    (net (code "267") (name "unconnected-(U3-PB6-I2C1SCL{slash}TIM4CH1-USART1TX-Pad58)") (class "Default")
      (node (ref "U3") (pin "58") (pinfunction "PB6-I2C1SCL/TIM4CH1-USART1TX_58") (pintype "bidirectional"))
    )
    (net (code "268") (name "unconnected-(U3-PB7-I2C1SDA{slash}TIM4CH2-USART1RX-Pad59)") (class "Default")
      (node (ref "U3") (pin "59") (pinfunction "PB7-I2C1SDA/TIM4CH2-USART1RX_59") (pintype "bidirectional"))
    )
    (net (code "269") (name "unconnected-(U3-PC8-TIM3CH3-Pad39)") (class "Default")
      (node (ref "U3") (pin "39") (pinfunction "PC8-TIM3CH3_39") (pintype "bidirectional"))
    )
    (net (code "270") (name "unconnected-(U3-PC9-TIM3CH4-Pad40)") (class "Default")
      (node (ref "U3") (pin "40") (pinfunction "PC9-TIM3CH4_40") (pintype "bidirectional"))
    )
    (net (code "271") (name "unconnected-(U3-PC13-TAMPER-RTC-Pad2)") (class "Default")
      (node (ref "U3") (pin "2") (pinfunction "PC13-TAMPER-RTC_2") (pintype "bidirectional"))
    )
    (net (code "272") (name "unconnected-(U3-PC14-OSC32_IN-Pad3)") (class "Default")
      (node (ref "U3") (pin "3") (pinfunction "PC14-OSC32_IN_3") (pintype "bidirectional"))
    )
    (net (code "273") (name "unconnected-(U3-PC15-OSC32_OUT-Pad4)") (class "Default")
      (node (ref "U3") (pin "4") (pinfunction "PC15-OSC32_OUT_4") (pintype "bidirectional"))
    )
    (net (code "274") (name "unconnected-(U3-PD1-OSC_OUT-CANTX-Pad6)") (class "Default")
      (node (ref "U3") (pin "6") (pinfunction "PD1-OSC_OUT-CANTX_6") (pintype "output"))
    )
    (net (code "275") (name "unconnected-(U3-PD2-TIM3ETR-Pad54)") (class "Default")
      (node (ref "U3") (pin "54") (pinfunction "PD2-TIM3ETR_54") (pintype "bidirectional"))
    )
    (net (code "276") (name "unconnected-(U7-AC8-Pad32)") (class "Default")
      (node (ref "U7") (pin "32") (pinfunction "AC8_32") (pintype "bidirectional"))
    )
    (net (code "277") (name "unconnected-(U7-AC9-Pad33)") (class "Default")
      (node (ref "U7") (pin "33") (pinfunction "AC9_33") (pintype "bidirectional"))
    )
    (net (code "278") (name "unconnected-(U10C-NC1-Pad22)") (class "Default")
      (node (ref "U10") (pin "22") (pinfunction "NC1_22") (pintype "bidirectional"))
    )
    (net (code "279") (name "unconnected-(U10C-NC2-Pad28)") (class "Default")
      (node (ref "U10") (pin "28") (pinfunction "NC2_28") (pintype "bidirectional"))
    )
    (net (code "280") (name "unconnected-(U12-NC-Pad4)") (class "Default")
      (node (ref "U12") (pin "4") (pinfunction "NC_4") (pintype "bidirectional"))
    )
  )
)
